# 3020_-0113.net
KiCad netlist of a schematic drawn in EasyEDA Pro
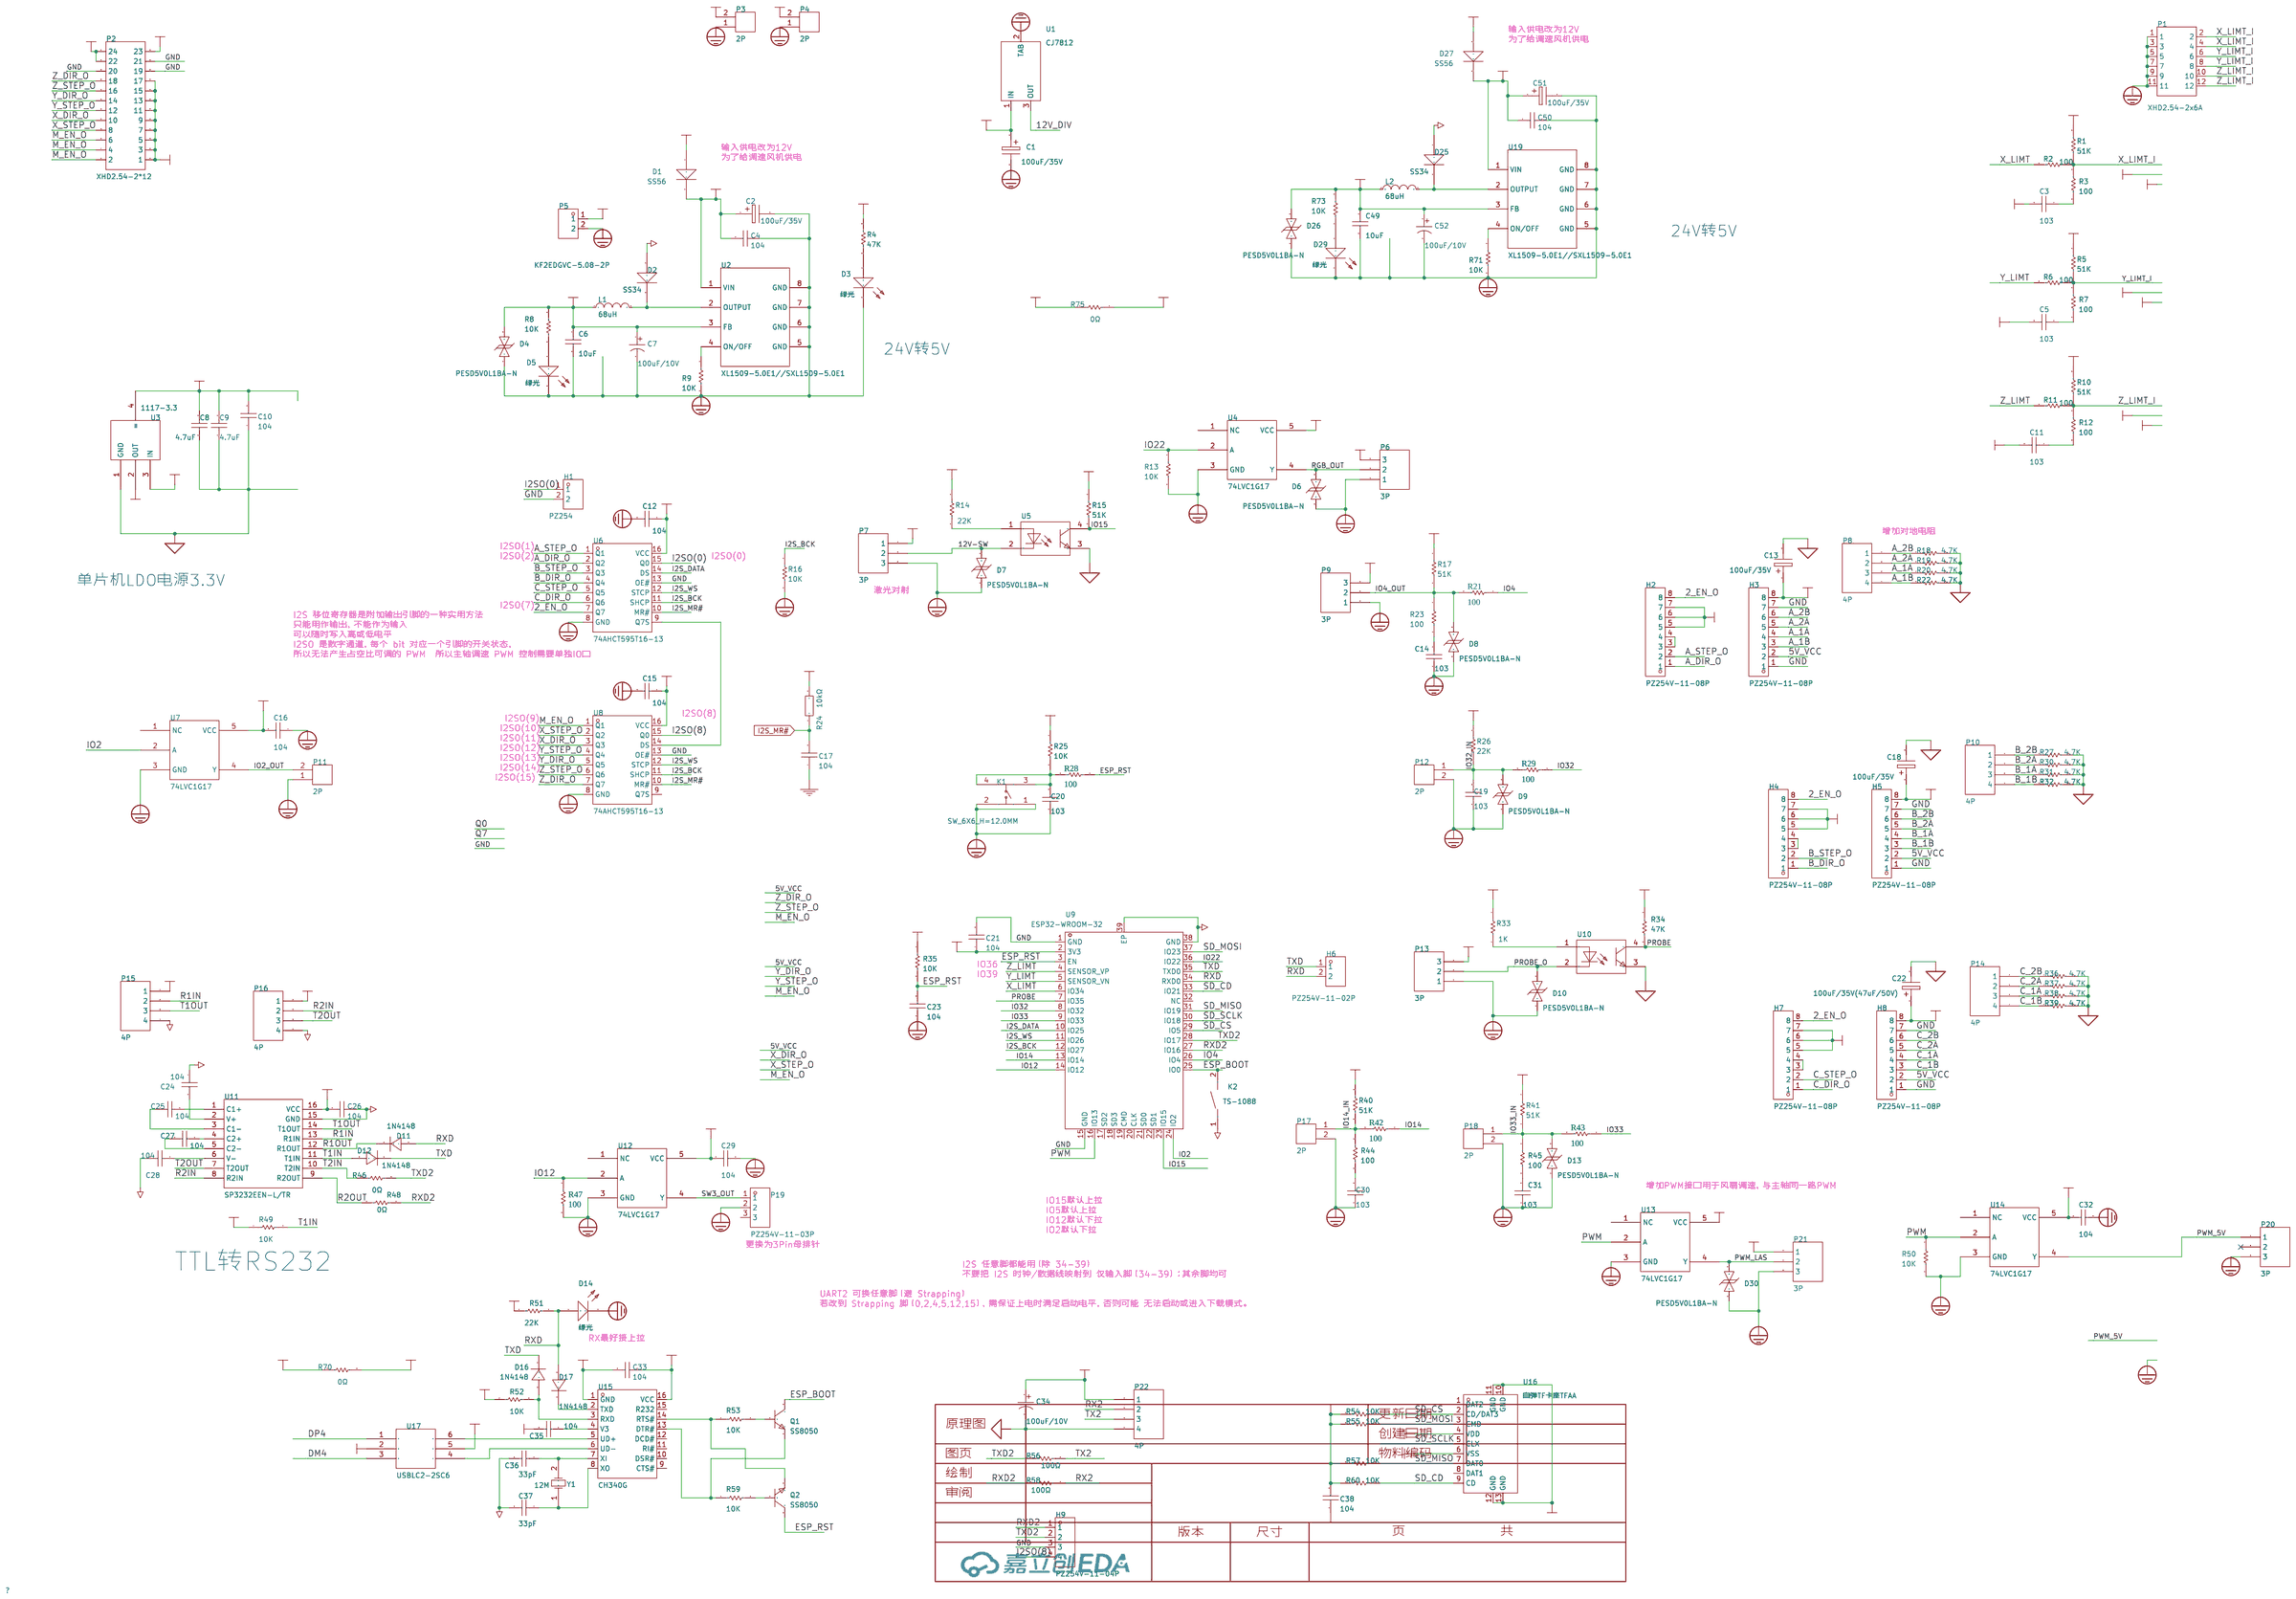
[diagram p0: 电源]
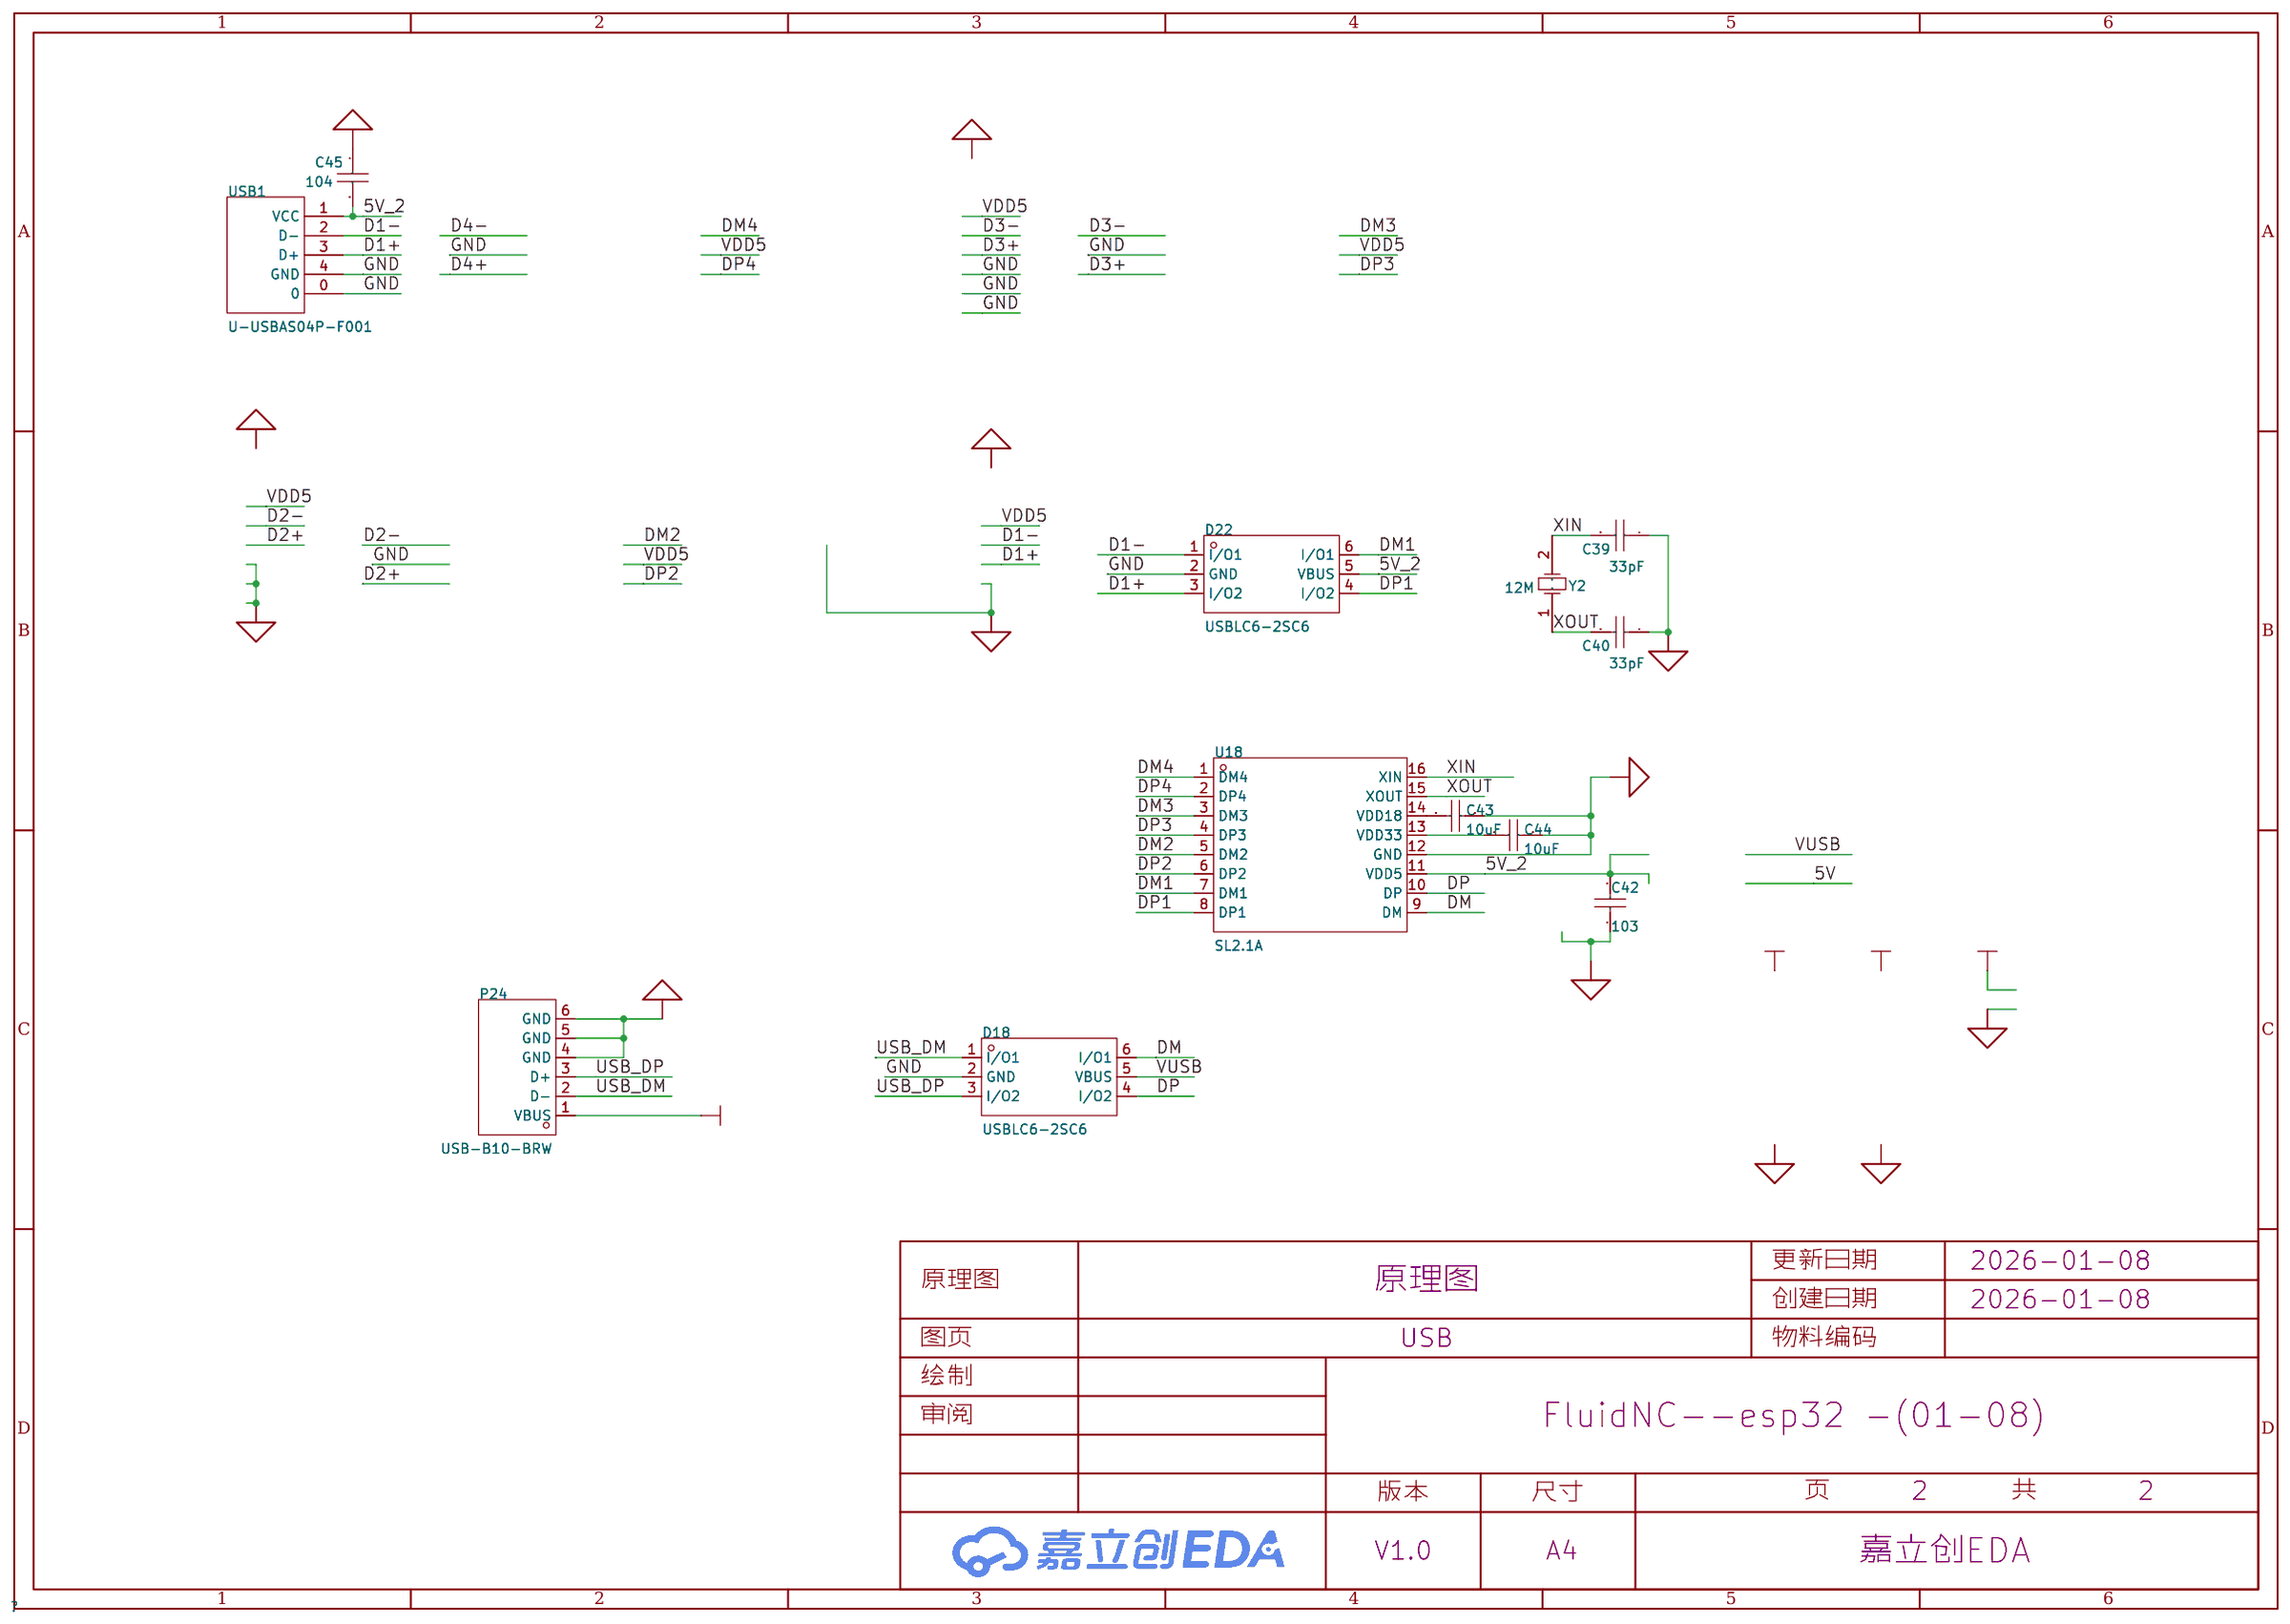
[diagram p1: USB]

(export (version "E")
  (design (tool "Eeschema 10.0.6"))
  (components
    (comp (ref "C1")
      (value "100uF/35V")
      (footprint "easyedapro:电解电容贴片10x10")
      (libsource (lib "easyedapro") (part "ELECTRO1"))
    )
    (comp (ref "C2")
      (value "100uF/35V")
      (footprint "easyedapro:电解电容贴片10x10")
      (libsource (lib "easyedapro") (part "ELECTRO1"))
    )
    (comp (ref "C3") (value "103") (footprint "easyedapro:11") (libsource (lib "") (part "CAP_1")))
    (comp (ref "C4")
      (value "104")
      (footprint "easyedapro:0603C")
      (description "Capacitor (Semiconductor SIM Model)")
      (libsource (lib "easyedapro") (part "Cap Semi"))
    )
    (comp (ref "C5") (value "103") (footprint "easyedapro:11") (libsource (lib "") (part "CAP_1")))
    (comp (ref "C6") (value "10uF") (libsource (lib "easyedapro") (part "CAP")))
    (comp (ref "C7")
      (value "100uF/10V")
      (footprint "easyedapro:CAP-SMD_BD5.0-L5.3-W5.3-RD")
      (fields (field (name "Manufacturer Part") "CS1A101M-CRD54") (field (name "Manufacturer") "ST(先科)"))
      (libsource (lib "easyedapro") (part "CS1A101M-CRD54"))
    )
    (comp (ref "C8") (value "4.7uF") (libsource (lib "easyedapro") (part "CAP")))
    (comp (ref "C9") (value "4.7uF") (libsource (lib "easyedapro") (part "CAP")))
    (comp (ref "C10")
      (value "104")
      (footprint "easyedapro:0603C")
      (description "Capacitor (Semiconductor SIM Model)")
      (libsource (lib "easyedapro") (part "Cap Semi"))
    )
    (comp (ref "C11") (value "103") (footprint "easyedapro:11") (libsource (lib "") (part "CAP_1")))
    (comp (ref "C12")
      (value "104")
      (footprint "easyedapro:0603C")
      (description "Capacitor (Semiconductor SIM Model)")
      (libsource (lib "easyedapro") (part "Cap Semi"))
    )
    (comp (ref "C13")
      (value "100uF/35V")
      (footprint "easyedapro:电解电容贴片10x10")
      (libsource (lib "easyedapro") (part "ELECTRO1"))
    )
    (comp (ref "C14") (value "103") (footprint "easyedapro:11") (libsource (lib "") (part "CAP_1")))
    (comp (ref "C15")
      (value "104")
      (footprint "easyedapro:0603C")
      (description "Capacitor (Semiconductor SIM Model)")
      (libsource (lib "easyedapro") (part "Cap Semi"))
    )
    (comp (ref "C16")
      (value "104")
      (footprint "easyedapro:0603C")
      (description "Capacitor (Semiconductor SIM Model)")
      (libsource (lib "easyedapro") (part "Cap Semi"))
    )
    (comp (ref "C17")
      (value "104")
      (footprint "easyedapro:0603C")
      (description "Capacitor (Semiconductor SIM Model)")
      (libsource (lib "easyedapro") (part "Cap Semi"))
    )
    (comp (ref "C18")
      (value "100uF/35V")
      (footprint "easyedapro:电解电容贴片10x10")
      (libsource (lib "easyedapro") (part "ELECTRO1"))
    )
    (comp (ref "C19") (value "103") (footprint "easyedapro:11") (libsource (lib "") (part "CAP_1")))
    (comp (ref "C20") (value "103") (footprint "easyedapro:11") (libsource (lib "") (part "CAP_1")))
    (comp (ref "C21")
      (value "104")
      (footprint "easyedapro:0603C")
      (description "Capacitor (Semiconductor SIM Model)")
      (libsource (lib "easyedapro") (part "Cap Semi"))
    )
    (comp (ref "C22")
      (value "100uF/35V(47uF/50V)")
      (footprint "easyedapro:电解电容贴片10x10")
      (libsource (lib "easyedapro") (part "ELECTRO1"))
    )
    (comp (ref "C23")
      (value "104")
      (footprint "easyedapro:0603C")
      (description "Capacitor (Semiconductor SIM Model)")
      (libsource (lib "easyedapro") (part "Cap Semi"))
    )
    (comp (ref "C24")
      (value "104")
      (footprint "easyedapro:0603C")
      (description "Capacitor (Semiconductor SIM Model)")
      (libsource (lib "easyedapro") (part "Cap Semi"))
    )
    (comp (ref "C25")
      (value "104")
      (footprint "easyedapro:0603C")
      (description "Capacitor (Semiconductor SIM Model)")
      (libsource (lib "easyedapro") (part "Cap Semi"))
    )
    (comp (ref "C26")
      (value "104")
      (footprint "easyedapro:0603C")
      (description "Capacitor (Semiconductor SIM Model)")
      (libsource (lib "easyedapro") (part "Cap Semi"))
    )
    (comp (ref "C27")
      (value "104")
      (footprint "easyedapro:0603C")
      (description "Capacitor (Semiconductor SIM Model)")
      (libsource (lib "easyedapro") (part "Cap Semi"))
    )
    (comp (ref "C28")
      (value "104")
      (footprint "easyedapro:0603C")
      (description "Capacitor (Semiconductor SIM Model)")
      (libsource (lib "easyedapro") (part "Cap Semi"))
    )
    (comp (ref "C29")
      (value "104")
      (footprint "easyedapro:0603C")
      (description "Capacitor (Semiconductor SIM Model)")
      (libsource (lib "easyedapro") (part "Cap Semi"))
    )
    (comp (ref "C30") (value "103") (footprint "easyedapro:11") (libsource (lib "") (part "CAP_1")))
    (comp (ref "C31") (value "103") (footprint "easyedapro:11") (libsource (lib "") (part "CAP_1")))
    (comp (ref "C32")
      (value "104")
      (footprint "easyedapro:0603C")
      (description "Capacitor (Semiconductor SIM Model)")
      (libsource (lib "easyedapro") (part "Cap Semi"))
    )
    (comp (ref "C33")
      (value "104")
      (footprint "easyedapro:0603C")
      (description "Capacitor (Semiconductor SIM Model)")
      (libsource (lib "easyedapro") (part "Cap Semi"))
    )
    (comp (ref "C34")
      (value "100uF/10V")
      (footprint "easyedapro:CAP-SMD_BD5.0-L5.3-W5.3-RD")
      (fields (field (name "Manufacturer Part") "CS1A101M-CRD54") (field (name "Manufacturer") "ST(先科)"))
      (libsource (lib "easyedapro") (part "CS1A101M-CRD54"))
    )
    (comp (ref "C35")
      (value "104")
      (footprint "easyedapro:0603C")
      (description "Capacitor (Semiconductor SIM Model)")
      (libsource (lib "easyedapro") (part "Cap Semi"))
    )
    (comp (ref "C36")
      (value "18pF")
      (footprint "easyedapro:0603C")
      (description "Capacitor (Semiconductor SIM Model)")
      (libsource (lib "easyedapro") (part "Cap Semi"))
    )
    (comp (ref "C37")
      (value "18pF")
      (footprint "easyedapro:0603C")
      (description "Capacitor (Semiconductor SIM Model)")
      (libsource (lib "easyedapro") (part "Cap Semi"))
    )
    (comp (ref "C38")
      (value "104")
      (footprint "easyedapro:11")
      (description "Capacitor (Semiconductor SIM Model)")
      (libsource (lib "easyedapro") (part "Cap Semi"))
    )
    (comp (ref "C49") (value "10uF") (libsource (lib "easyedapro") (part "CAP")))
    (comp (ref "C50")
      (value "104")
      (footprint "easyedapro:0603C")
      (description "Capacitor (Semiconductor SIM Model)")
      (libsource (lib "easyedapro") (part "Cap Semi"))
    )
    (comp (ref "C51")
      (value "100uF/35V")
      (footprint "easyedapro:电解电容贴片10x10")
      (libsource (lib "easyedapro") (part "ELECTRO1"))
    )
    (comp (ref "C52")
      (value "100uF/10V")
      (footprint "easyedapro:CAP-SMD_BD5.0-L5.3-W5.3-RD")
      (fields (field (name "Manufacturer Part") "CS1A101M-CRD54") (field (name "Manufacturer") "ST(先科)"))
      (libsource (lib "easyedapro") (part "CS1A101M-CRD54"))
    )
    (comp (ref "D1") (value "SS56") (footprint "easyedapro:SMA") (libsource (lib "") (part "1N4148_1")))
    (comp (ref "D2") (value "SS34") (libsource (lib "easyedapro") (part "1N4148")))
    (comp (ref "D3")
      (value "绿光")
      (footprint "easyedapro:0603LED")
      (libsource (lib "easyedapro") (part "LED"))
    )
    (comp (ref "D4")
      (value "PESD5V0L1BA-N")
      (footprint "easyedapro:SOD-523_L1.2-W0.8-LS1.6-BI")
      (description "极性:Bidirectional;反向关断电压（典型值）:5V (Max);击穿电压（最小值）:6V;箝位电压:15V;峰值脉冲电流（10/1000us）:5A (8/20us);")
      (fields (field (name "Manufacturer") "BORN伯恩半导体"))
      (libsource (lib "easyedapro") (part "PESD5V0S1BBN"))
    )
    (comp (ref "D5")
      (value "绿光")
      (footprint "easyedapro:0603LED")
      (libsource (lib "easyedapro") (part "LED"))
    )
    (comp (ref "D6")
      (value "PESD5V0L1BA-N")
      (footprint "easyedapro:SOD-523_L1.2-W0.8-LS1.6-BI")
      (description "极性:Bidirectional;反向关断电压（典型值）:5V (Max);击穿电压（最小值）:6V;箝位电压:15V;峰值脉冲电流（10/1000us）:5A (8/20us);")
      (fields (field (name "Manufacturer") "BORN伯恩半导体"))
      (libsource (lib "easyedapro") (part "PESD5V0S1BBN"))
    )
    (comp (ref "D7")
      (value "PESD5V0L1BA-N")
      (footprint "easyedapro:SOD-523_L1.2-W0.8-LS1.6-BI")
      (description "极性:Bidirectional;反向关断电压（典型值）:5V (Max);击穿电压（最小值）:6V;箝位电压:15V;峰值脉冲电流（10/1000us）:5A (8/20us);")
      (fields (field (name "Manufacturer") "BORN伯恩半导体"))
      (libsource (lib "easyedapro") (part "PESD5V0S1BBN"))
    )
    (comp (ref "D8")
      (value "PESD5V0L1BA-N")
      (footprint "easyedapro:SOD-523_L1.2-W0.8-LS1.6-BI")
      (description "极性:Bidirectional;反向关断电压（典型值）:5V (Max);击穿电压（最小值）:6V;箝位电压:15V;峰值脉冲电流（10/1000us）:5A (8/20us);")
      (fields (field (name "Manufacturer") "BORN伯恩半导体"))
      (libsource (lib "easyedapro") (part "PESD5V0S1BBN"))
    )
    (comp (ref "D9")
      (value "PESD5V0L1BA-N")
      (footprint "easyedapro:SOD-523_L1.2-W0.8-LS1.6-BI")
      (description "极性:Bidirectional;反向关断电压（典型值）:5V (Max);击穿电压（最小值）:6V;箝位电压:15V;峰值脉冲电流（10/1000us）:5A (8/20us);")
      (fields (field (name "Manufacturer") "BORN伯恩半导体"))
      (libsource (lib "easyedapro") (part "PESD5V0S1BBN"))
    )
    (comp (ref "D10")
      (value "PESD5V0L1BA-N")
      (footprint "easyedapro:SOD-523_L1.2-W0.8-LS1.6-BI")
      (description "极性:Bidirectional;反向关断电压（典型值）:5V (Max);击穿电压（最小值）:6V;箝位电压:15V;峰值脉冲电流（10/1000us）:5A (8/20us);")
      (fields (field (name "Manufacturer") "BORN伯恩半导体"))
      (libsource (lib "easyedapro") (part "PESD5V0S1BBN"))
    )
    (comp (ref "D11")
      (value "1N4148")
      (footprint "easyedapro:SOD-123_L2.8-W1.8-LS3.7-RD")
      (fields (field (name "Manufacturer") "VISHAY(威世)"))
      (libsource (lib "easyedapro") (part "1N4148W-E3-08"))
    )
    (comp (ref "D12")
      (value "1N4148")
      (footprint "easyedapro:SOD-123_L2.8-W1.8-LS3.7-RD")
      (fields (field (name "Manufacturer") "VISHAY(威世)"))
      (libsource (lib "easyedapro") (part "1N4148W-E3-08"))
    )
    (comp (ref "D13")
      (value "PESD5V0L1BA-N")
      (footprint "easyedapro:SOD-523_L1.2-W0.8-LS1.6-BI")
      (description "极性:Bidirectional;反向关断电压（典型值）:5V (Max);击穿电压（最小值）:6V;箝位电压:15V;峰值脉冲电流（10/1000us）:5A (8/20us);")
      (fields (field (name "Manufacturer") "BORN伯恩半导体"))
      (libsource (lib "easyedapro") (part "PESD5V0S1BBN"))
    )
    (comp (ref "D14")
      (value "绿光")
      (footprint "easyedapro:0603LED")
      (libsource (lib "easyedapro") (part "LED"))
    )
    (comp (ref "D16")
      (value "1N4148")
      (footprint "easyedapro:SOD-123_L2.8-W1.8-LS3.7-RD")
      (fields (field (name "Manufacturer") "VISHAY(威世)"))
      (libsource (lib "easyedapro") (part "1N4148W-E3-08"))
    )
    (comp (ref "D17")
      (value "1N4148")
      (footprint "easyedapro:SOD-123_L2.8-W1.8-LS3.7-RD")
      (fields (field (name "Manufacturer") "VISHAY(威世)"))
      (libsource (lib "easyedapro") (part "1N4148W-E3-08"))
    )
    (comp (ref "D25") (value "SS34") (libsource (lib "easyedapro") (part "1N4148")))
    (comp (ref "D26")
      (value "PESD5V0L1BA-N")
      (footprint "easyedapro:SOD-523_L1.2-W0.8-LS1.6-BI")
      (description "极性:Bidirectional;反向关断电压（典型值）:5V (Max);击穿电压（最小值）:6V;箝位电压:15V;峰值脉冲电流（10/1000us）:5A (8/20us);")
      (fields (field (name "Manufacturer") "BORN伯恩半导体"))
      (libsource (lib "easyedapro") (part "PESD5V0S1BBN"))
    )
    (comp (ref "D27") (value "SS56") (footprint "easyedapro:SMA") (libsource (lib "") (part "1N4148_1")))
    (comp (ref "D29")
      (value "绿光")
      (footprint "easyedapro:0603LED")
      (libsource (lib "easyedapro") (part "LED"))
    )
    (comp (ref "D30")
      (value "PESD5V0L1BA-N")
      (footprint "easyedapro:SOD-523_L1.2-W0.8-LS1.6-BI")
      (description "极性:Bidirectional;反向关断电压（典型值）:5V (Max);击穿电压（最小值）:6V;箝位电压:15V;峰值脉冲电流（10/1000us）:5A (8/20us);")
      (fields (field (name "Manufacturer") "BORN伯恩半导体"))
      (libsource (lib "easyedapro") (part "PESD5V0S1BBN"))
    )
    (comp (ref "H1")
      (value "PZ254")
      (footprint "easyedapro:HDR-TH_2P-P2.54-V-M")
      (fields (field (name "Manufacturer") "XFCN(兴飞)"))
      (libsource (lib "easyedapro") (part "PZ254V-11-02P"))
    )
    (comp (ref "H2")
      (value "PZ254V-11-08P")
      (footprint "easyedapro:HDR-TH_8P-P2.54-V-M")
      (fields (field (name "Manufacturer") "XFCN(兴飞)"))
      (libsource (lib "easyedapro") (part "PZ254V-11-08P"))
    )
    (comp (ref "H3")
      (value "PZ254V-11-08P")
      (footprint "easyedapro:HDR-TH_8P-P2.54-V-M")
      (fields (field (name "Manufacturer") "XFCN(兴飞)"))
      (libsource (lib "easyedapro") (part "PZ254V-11-08P"))
    )
    (comp (ref "H4")
      (value "PZ254V-11-08P")
      (footprint "easyedapro:HDR-TH_8P-P2.54-V-M")
      (fields (field (name "Manufacturer") "XFCN(兴飞)"))
      (libsource (lib "easyedapro") (part "PZ254V-11-08P"))
    )
    (comp (ref "H5")
      (value "PZ254V-11-08P")
      (footprint "easyedapro:HDR-TH_8P-P2.54-V-M")
      (fields (field (name "Manufacturer") "XFCN(兴飞)"))
      (libsource (lib "easyedapro") (part "PZ254V-11-08P"))
    )
    (comp (ref "H6")
      (value "PZ254V-11-02P")
      (footprint "easyedapro:HDR-TH_2P-P2.54-V-M")
      (fields (field (name "Manufacturer") "XFCN(兴飞)"))
      (libsource (lib "easyedapro") (part "PZ254V-11-02P"))
    )
    (comp (ref "H7")
      (value "PZ254V-11-08P")
      (footprint "easyedapro:HDR-TH_8P-P2.54-V-M")
      (fields (field (name "Manufacturer") "XFCN(兴飞)"))
      (libsource (lib "easyedapro") (part "PZ254V-11-08P"))
    )
    (comp (ref "H8")
      (value "PZ254V-11-08P")
      (footprint "easyedapro:HDR-TH_8P-P2.54-V-M")
      (fields (field (name "Manufacturer") "XFCN(兴飞)"))
      (libsource (lib "easyedapro") (part "PZ254V-11-08P"))
    )
    (comp (ref "H9")
      (value "PZ254V-11-04P")
      (footprint "easyedapro:HDR-TH_4P-P2.54-V-M")
      (fields (field (name "Manufacturer") "XFCN(兴飞)"))
      (libsource (lib "easyedapro") (part "PZ254V-11-04P_C2691448"))
    )
    (comp (ref "K1")
      (value "SW_6X6_H=12.0MM")
      (footprint "easyedapro:KEY-SMD_4P-L6.0-W6.0-P4.50-LS9.0")
      (libsource (lib "easyedapro") (part "SW_6X6_H=12.0MM"))
    )
    (comp (ref "K2")
      (value "TS-1088")
      (footprint "easyedapro:SW-SMD_L3.9-W3.0-P4.45")
      (fields (field (name "Manufacturer") "XUNPU(讯普)"))
      (libsource (lib "easyedapro") (part "TS-1088-AR02016"))
    )
    (comp (ref "L1")
      (value "68uH")
      (footprint "easyedapro:IND-SMD_L7.0-W7.0_SMDRI74-330MT")
      (description "电感值:33uH;精度:±20%;额定电流:960mA;饱和电流(Isat):1.8A;类型:屏蔽电感;")
      (fields (field (name "Manufacturer Part") "SMDRI74-330MT") (field (name "Manufacturer") "SXN(顺翔诺)"))
      (libsource (lib "easyedapro") (part "SMDRI74-330MT"))
    )
    (comp (ref "L2")
      (value "68uH")
      (footprint "easyedapro:IND-SMD_L7.0-W7.0_SMDRI74-330MT")
      (description "电感值:33uH;精度:±20%;额定电流:960mA;饱和电流(Isat):1.8A;类型:屏蔽电感;")
      (fields (field (name "Manufacturer Part") "SMDRI74-330MT") (field (name "Manufacturer") "SXN(顺翔诺)"))
      (libsource (lib "easyedapro") (part "SMDRI74-330MT"))
    )
    (comp (ref "P1")
      (value "XHD2.54-2x6A")
      (footprint "easyedapro:CONN-TH_12P-P2.50_HC-XHD2.54-2X6A")
      (fields (field (name "Manufacturer") "HC(虹成电子)"))
      (libsource (lib "easyedapro") (part "HC-XHD2.54-2X6A"))
    )
    (comp (ref "P2")
      (value "XHD2.54-2*12")
      (footprint "easyedapro:IDC-TH_24P-P2.54-V-R2-C12-S2.54")
      (fields (field (name "Manufacturer") "BOOMELE(博穆精密)"))
      (libsource (lib "easyedapro") (part "HDR-IDC-2.54-2X12P"))
    )
    (comp (ref "P3") (value "2P") (libsource (lib "easyedapro") (part "2P")))
    (comp (ref "P4") (value "2P") (libsource (lib "easyedapro") (part "2P")))
    (comp (ref "P5")
      (value "KF2EDGVC-5.08-2P")
      (footprint "easyedapro:CONN-TH_P5.08_KF2EDGVC-5.08-2P")
      (description "连接器类型:板端/插座-闭口;结构:1x2P;间距:5.08mm;颜色:绿色;安装方式:直针;排数:1;每排PIN数:2;额定电流:15A;额定电压:300V;工作温度:-40°C~+105°C;")
      (fields (field (name "Manufacturer") "KEFA(科发)"))
      (libsource (lib "easyedapro") (part "KF2EDGVC-5.08-2P"))
    )
    (comp (ref "P6")
      (value "3P")
      (footprint "easyedapro:HDR1X3_CON")
      (libsource (lib "easyedapro") (part "3P"))
    )
    (comp (ref "P7")
      (value "3P")
      (footprint "easyedapro:HDR1X3_CON")
      (libsource (lib "easyedapro") (part "3P"))
    )
    (comp (ref "P8")
      (value "4P")
      (footprint "easyedapro:HDR1X4_CON")
      (libsource (lib "easyedapro") (part "4P"))
    )
    (comp (ref "P9")
      (value "3P")
      (footprint "easyedapro:HDR1X3_CON")
      (libsource (lib "easyedapro") (part "3P"))
    )
    (comp (ref "P10")
      (value "4P")
      (footprint "easyedapro:HDR1X4_CON")
      (libsource (lib "easyedapro") (part "4P"))
    )
    (comp (ref "P11") (value "2P") (libsource (lib "easyedapro") (part "2P")))
    (comp (ref "P12") (value "2P") (libsource (lib "easyedapro") (part "2P")))
    (comp (ref "P13")
      (value "3P")
      (footprint "easyedapro:HDR1X3_CON")
      (libsource (lib "easyedapro") (part "3P"))
    )
    (comp (ref "P14")
      (value "4P")
      (footprint "easyedapro:HDR1X4_CON")
      (libsource (lib "easyedapro") (part "4P"))
    )
    (comp (ref "P15")
      (value "4P")
      (footprint "easyedapro:HDR1X4_CON")
      (libsource (lib "easyedapro") (part "4P"))
    )
    (comp (ref "P16")
      (value "4P")
      (footprint "easyedapro:HDR1X4_CON")
      (libsource (lib "easyedapro") (part "4P"))
    )
    (comp (ref "P17") (value "2P") (libsource (lib "easyedapro") (part "2P")))
    (comp (ref "P18") (value "2P") (libsource (lib "easyedapro") (part "2P")))
    (comp (ref "P19")
      (value "PZ254V-11-03P")
      (footprint "easyedapro:HDR-TH_3P-P2.54-V-M")
      (fields (field (name "Manufacturer") "XFCN(兴飞)"))
      (libsource (lib "easyedapro") (part "PZ254V-11-03P"))
    )
    (comp (ref "P20")
      (value "3P")
      (footprint "easyedapro:HDR1X3_CON")
      (libsource (lib "easyedapro") (part "3P"))
    )
    (comp (ref "P21")
      (value "3P")
      (footprint "easyedapro:HDR1X3_CON")
      (libsource (lib "easyedapro") (part "3P"))
    )
    (comp (ref "P22")
      (value "4P")
      (footprint "easyedapro:HDR1X4_CON")
      (libsource (lib "easyedapro") (part "4P"))
    )
    (comp (ref "Q1")
      (value "SS8050")
      (footprint "easyedapro:SOT-23-3_L2.9-W1.3-P1.90-LS2.4-BR")
      (fields (field (name "Manufacturer") "Doeshare(德芯)"))
      (libsource (lib "easyedapro") (part "SS8050_C2931717"))
    )
    (comp (ref "Q2")
      (value "SS8050")
      (footprint "easyedapro:SOT-23-3_L2.9-W1.3-P1.90-LS2.4-BR")
      (fields (field (name "Manufacturer") "Doeshare(德芯)"))
      (libsource (lib "easyedapro") (part "SS8050_C2931717"))
    )
    (comp (ref "R1")
      (value "51K")
      (footprint "easyedapro:10")
      (description "Resistor")
      (libsource (lib "easyedapro") (part "RES"))
    )
    (comp (ref "R2")
      (value "100")
      (footprint "easyedapro:10")
      (description "Resistor")
      (libsource (lib "easyedapro") (part "RES"))
    )
    (comp (ref "R3")
      (value "100")
      (footprint "easyedapro:10")
      (description "Resistor")
      (libsource (lib "easyedapro") (part "RES"))
    )
    (comp (ref "R4")
      (value "47K")
      (footprint "easyedapro:0603R")
      (description "Resistor")
      (libsource (lib "easyedapro") (part "RES"))
    )
    (comp (ref "R5")
      (value "51K")
      (footprint "easyedapro:10")
      (description "Resistor")
      (libsource (lib "easyedapro") (part "RES"))
    )
    (comp (ref "R6")
      (value "100")
      (footprint "easyedapro:10")
      (description "Resistor")
      (libsource (lib "easyedapro") (part "RES"))
    )
    (comp (ref "R7")
      (value "100")
      (footprint "easyedapro:10")
      (description "Resistor")
      (libsource (lib "easyedapro") (part "RES"))
    )
    (comp (ref "R8")
      (value "10K")
      (footprint "easyedapro:0603R")
      (description "Resistor")
      (libsource (lib "easyedapro") (part "RES"))
    )
    (comp (ref "R9")
      (value "10K")
      (footprint "easyedapro:0603R")
      (description "Resistor")
      (libsource (lib "easyedapro") (part "RES"))
    )
    (comp (ref "R10")
      (value "51K")
      (footprint "easyedapro:10")
      (description "Resistor")
      (libsource (lib "easyedapro") (part "RES"))
    )
    (comp (ref "R11")
      (value "100")
      (footprint "easyedapro:10")
      (description "Resistor")
      (libsource (lib "easyedapro") (part "RES"))
    )
    (comp (ref "R12")
      (value "100")
      (footprint "easyedapro:10")
      (description "Resistor")
      (libsource (lib "easyedapro") (part "RES"))
    )
    (comp (ref "R13")
      (value "10K")
      (description "Resistor")
      (fields (field (name "Publisher") "Altium Limited"))
      (libsource (lib "") (part "RES_1"))
    )
    (comp (ref "R14")
      (value "22K")
      (footprint "easyedapro:0603R")
      (description "Resistor")
      (libsource (lib "easyedapro") (part "RES"))
    )
    (comp (ref "R15")
      (value "10K")
      (footprint "easyedapro:0603R")
      (description "Resistor")
      (libsource (lib "easyedapro") (part "RES"))
    )
    (comp (ref "R16")
      (value "10K")
      (footprint "easyedapro:0603R")
      (description "Resistor")
      (libsource (lib "easyedapro") (part "RES"))
    )
    (comp (ref "R17")
      (value "10K")
      (footprint "easyedapro:0603R")
      (description "Resistor")
      (libsource (lib "easyedapro") (part "RES"))
    )
    (comp (ref "R18")
      (value "10K")
      (footprint "easyedapro:0603R")
      (description "Resistor")
      (libsource (lib "easyedapro") (part "10K"))
    )
    (comp (ref "R19")
      (value "10K")
      (footprint "easyedapro:0603R")
      (description "Resistor")
      (libsource (lib "easyedapro") (part "10K"))
    )
    (comp (ref "R20")
      (value "10K")
      (footprint "easyedapro:0603R")
      (description "Resistor")
      (libsource (lib "easyedapro") (part "10K"))
    )
    (comp (ref "R21")
      (value "100")
      (description "Resistor")
      (fields (field (name "Publisher") "Altium Limited"))
      (libsource (lib "") (part "RES_1"))
    )
    (comp (ref "R22")
      (value "10K")
      (footprint "easyedapro:0603R")
      (description "Resistor")
      (libsource (lib "easyedapro") (part "10K"))
    )
    (comp (ref "R23")
      (value "100")
      (footprint "easyedapro:10")
      (description "Resistor")
      (libsource (lib "easyedapro") (part "RES"))
    )
    (comp (ref "R24")
      (value "10kΩ")
      (footprint "easyedapro:R0603")
      (fields (field (name "Manufacturer Part") "0603WAF1002T5E") (field (name "Manufacturer") "UniOhm"))
      (libsource (lib "easyedapro") (part "10kΩ"))
    )
    (comp (ref "R25")
      (value "10K")
      (footprint "easyedapro:0603R")
      (description "Resistor")
      (libsource (lib "easyedapro") (part "RES"))
    )
    (comp (ref "R26")
      (value "10K")
      (footprint "easyedapro:0603R")
      (description "Resistor")
      (libsource (lib "easyedapro") (part "RES"))
    )
    (comp (ref "R27")
      (value "10K")
      (footprint "easyedapro:0603R")
      (description "Resistor")
      (libsource (lib "easyedapro") (part "10K"))
    )
    (comp (ref "R28")
      (value "100")
      (description "Resistor")
      (fields (field (name "Publisher") "Altium Limited"))
      (libsource (lib "") (part "RES_1"))
    )
    (comp (ref "R29")
      (value "100")
      (description "Resistor")
      (fields (field (name "Publisher") "Altium Limited"))
      (libsource (lib "") (part "RES_1"))
    )
    (comp (ref "R30")
      (value "10K")
      (footprint "easyedapro:0603R")
      (description "Resistor")
      (libsource (lib "easyedapro") (part "10K"))
    )
    (comp (ref "R31")
      (value "10K")
      (footprint "easyedapro:0603R")
      (description "Resistor")
      (libsource (lib "easyedapro") (part "10K"))
    )
    (comp (ref "R32")
      (value "10K")
      (footprint "easyedapro:0603R")
      (description "Resistor")
      (libsource (lib "easyedapro") (part "10K"))
    )
    (comp (ref "R33")
      (value "1K")
      (footprint "easyedapro:0603R")
      (description "Resistor")
      (libsource (lib "easyedapro") (part "RES"))
    )
    (comp (ref "R34")
      (value "10K")
      (footprint "easyedapro:0603R")
      (description "Resistor")
      (libsource (lib "easyedapro") (part "RES"))
    )
    (comp (ref "R35")
      (value "10K")
      (footprint "easyedapro:0603R")
      (description "Resistor")
      (libsource (lib "easyedapro") (part "RES"))
    )
    (comp (ref "R36")
      (value "10K")
      (footprint "easyedapro:0603R")
      (description "Resistor")
      (libsource (lib "easyedapro") (part "10K"))
    )
    (comp (ref "R37")
      (value "10K")
      (footprint "easyedapro:0603R")
      (description "Resistor")
      (libsource (lib "easyedapro") (part "10K"))
    )
    (comp (ref "R38")
      (value "10K")
      (footprint "easyedapro:0603R")
      (description "Resistor")
      (libsource (lib "easyedapro") (part "10K"))
    )
    (comp (ref "R39")
      (value "10K")
      (footprint "easyedapro:0603R")
      (description "Resistor")
      (libsource (lib "easyedapro") (part "10K"))
    )
    (comp (ref "R40")
      (value "10K")
      (footprint "easyedapro:0603R")
      (description "Resistor")
      (libsource (lib "easyedapro") (part "RES"))
    )
    (comp (ref "R41")
      (value "10K")
      (footprint "easyedapro:0603R")
      (description "Resistor")
      (libsource (lib "easyedapro") (part "RES"))
    )
    (comp (ref "R42")
      (value "100")
      (description "Resistor")
      (fields (field (name "Publisher") "Altium Limited"))
      (libsource (lib "") (part "RES_1"))
    )
    (comp (ref "R43")
      (value "100")
      (description "Resistor")
      (fields (field (name "Publisher") "Altium Limited"))
      (libsource (lib "") (part "RES_1"))
    )
    (comp (ref "R44")
      (value "100")
      (footprint "easyedapro:10")
      (description "Resistor")
      (libsource (lib "easyedapro") (part "RES"))
    )
    (comp (ref "R45")
      (value "100")
      (footprint "easyedapro:10")
      (description "Resistor")
      (libsource (lib "easyedapro") (part "RES"))
    )
    (comp (ref "R46")
      (value "0Ω")
      (footprint "easyedapro:0603R")
      (description "Resistor")
      (libsource (lib "easyedapro") (part "RES"))
    )
    (comp (ref "R47")
      (value "100")
      (description "Resistor")
      (fields (field (name "Publisher") "Altium Limited"))
      (libsource (lib "") (part "RES_1"))
    )
    (comp (ref "R48")
      (value "0Ω")
      (footprint "easyedapro:0603R")
      (description "Resistor")
      (libsource (lib "easyedapro") (part "RES"))
    )
    (comp (ref "R49")
      (value "10K")
      (footprint "easyedapro:0603R")
      (description "Resistor")
      (libsource (lib "easyedapro") (part "RES"))
    )
    (comp (ref "R50")
      (value "10K")
      (description "Resistor")
      (fields (field (name "Publisher") "Altium Limited"))
      (libsource (lib "") (part "RES_1"))
    )
    (comp (ref "R51")
      (value "10K")
      (footprint "easyedapro:0603R")
      (description "Resistor")
      (libsource (lib "easyedapro") (part "RES"))
    )
    (comp (ref "R52")
      (value "10K")
      (footprint "easyedapro:0603R")
      (description "Resistor")
      (libsource (lib "easyedapro") (part "RES"))
    )
    (comp (ref "R53")
      (value "10K")
      (footprint "easyedapro:0603R")
      (description "Resistor")
      (libsource (lib "easyedapro") (part "RES"))
    )
    (comp (ref "R54")
      (value "10K")
      (footprint "easyedapro:10")
      (description "Resistor")
      (libsource (lib "easyedapro") (part "RES"))
    )
    (comp (ref "R55")
      (value "10K")
      (footprint "easyedapro:10")
      (description "Resistor")
      (libsource (lib "easyedapro") (part "RES"))
    )
    (comp (ref "R56")
      (value "100Ω")
      (footprint "easyedapro:0603R")
      (description "Resistor")
      (libsource (lib "easyedapro") (part "RES"))
    )
    (comp (ref "R57")
      (value "10K")
      (footprint "easyedapro:10")
      (description "Resistor")
      (libsource (lib "easyedapro") (part "RES"))
    )
    (comp (ref "R58")
      (value "100Ω")
      (footprint "easyedapro:0603R")
      (description "Resistor")
      (libsource (lib "easyedapro") (part "RES"))
    )
    (comp (ref "R59")
      (value "10K")
      (footprint "easyedapro:0603R")
      (description "Resistor")
      (libsource (lib "easyedapro") (part "RES"))
    )
    (comp (ref "R60")
      (value "10K")
      (footprint "easyedapro:10")
      (description "Resistor")
      (libsource (lib "easyedapro") (part "RES"))
    )
    (comp (ref "R70")
      (value "0Ω")
      (footprint "easyedapro:0603R")
      (description "Resistor")
      (libsource (lib "easyedapro") (part "RES"))
    )
    (comp (ref "R71")
      (value "10K")
      (footprint "easyedapro:0603R")
      (description "Resistor")
      (libsource (lib "easyedapro") (part "RES"))
    )
    (comp (ref "R73")
      (value "10K")
      (footprint "easyedapro:0603R")
      (description "Resistor")
      (libsource (lib "easyedapro") (part "RES"))
    )
    (comp (ref "R75")
      (value "0Ω")
      (footprint "easyedapro:0603R")
      (description "Resistor")
      (libsource (lib "easyedapro") (part "RES"))
    )
    (comp (ref "U1")
      (value "CJ7812")
      (footprint "easyedapro:TO-263-2_L10.1-W9.1-P5.08-LS15.2-TL")
      (description "输出类型:固定;工作电压:35V;输出电压:12V;输出电流:1.5A;电源纹波抑制比(PSRR):71dB@(120Hz);输出极性:正极;")
      (fields (field (name "Manufacturer") "CJ(江苏长电/长晶)"))
      (libsource (lib "easyedapro") (part "CJ7812_C145151"))
    )
    (comp (ref "U2")
      (value "XL1509-5.0E1//SXL1509-5.0E1")
      (footprint "easyedapro:SOIC-8_L5.0-W4.0-P1.27-LS6.0-BL")
      (description "功能类型:降压型;同步整流:-;输出通道数:-;拓扑结构:-;输入电压:-;输出电流(最大值):-;开关频率:-;")
      (fields (field (name "Manufacturer") "XLSEMI(芯龙)"))
      (libsource (lib "easyedapro") (part "XL1509-5.0E1"))
    )
    (comp (ref "U3")
      (value "1117-3.3")
      (footprint "easyedapro:SOT-223")
      (libsource (lib "easyedapro") (part "LM1117"))
    )
    (comp (ref "U4")
      (value "74LVC1G17")
      (footprint "easyedapro:SMD8")
      (libsource (lib "easyedapro") (part "74LVC1G04"))
    )
    (comp (ref "U5")
      (value "LTV-357T-C")
      (footprint "easyedapro:SOP-4_L4.4-W3.9-P2.54-LS7.0-TL")
      (fields (field (name "Manufacturer") "LITEON(光宝)"))
      (libsource (lib "easyedapro") (part "LTV-357T-C"))
    )
    (comp (ref "U6")
      (value "74AHCT595T16-13")
      (footprint "easyedapro:TSSOP-16_L5.0-W4.4-P0.65-LS6.4-BL")
      (description "功能:串行至串行或并行;工作电压:4.5V~5.5V;元件数:1;每个元件位数:8;")
      (fields (field (name "Manufacturer") "DIODES(美台)"))
      (libsource (lib "easyedapro") (part "74AHCT595T16-13"))
    )
    (comp (ref "U7")
      (value "74LVC1G17")
      (footprint "easyedapro:SMD8")
      (libsource (lib "easyedapro") (part "74LVC1G04"))
    )
    (comp (ref "U8")
      (value "74AHCT595T16-13")
      (footprint "easyedapro:TSSOP-16_L5.0-W4.4-P0.65-LS6.4-BL")
      (description "功能:串行至串行或并行;工作电压:4.5V~5.5V;元件数:1;每个元件位数:8;")
      (fields (field (name "Manufacturer") "DIODES(美台)"))
      (libsource (lib "easyedapro") (part "74AHCT595T16-13"))
    )
    (comp (ref "U9")
      (value "ESP32-WROOM-32")
      (footprint "easyedapro:WIFIM-SMD_ESP-WROOM-32")
      (description "WiFi+双模蓝牙 双核CPU 网口 顶配MCU 低功耗蓝牙 ESP32系列ESP-WROOM-32模组/ESP-32S 4MB")
      (fields (field (name "Manufacturer") "ESPRESSIF(乐鑫)"))
      (libsource (lib "easyedapro") (part "ESP-WROOM-32"))
    )
    (comp (ref "U10")
      (value "LTV-357T-C")
      (footprint "easyedapro:SOP-4_L4.4-W3.9-P2.54-LS7.0-TL")
      (fields (field (name "Manufacturer") "LITEON(光宝)"))
      (libsource (lib "easyedapro") (part "LTV-357T-C"))
    )
    (comp (ref "U11")
      (value "SP3232EEN-L/TR")
      (footprint "easyedapro:SOIC-16_L9.9-W3.9-P1.27-LS6.0-BL")
      (description "类型:收发器;数据速率:235Kbps;")
      (fields (field (name "Manufacturer") "MaxLinear(迈凌)"))
      (libsource (lib "easyedapro") (part "SP3232EEN-L/TR"))
    )
    (comp (ref "U12")
      (value "74LVC1G17")
      (footprint "easyedapro:SMD8")
      (libsource (lib "easyedapro") (part "74LVC1G04"))
    )
    (comp (ref "U13")
      (value "74LVC1G17")
      (footprint "easyedapro:SMD8")
      (libsource (lib "easyedapro") (part "74LVC1G04"))
    )
    (comp (ref "U14")
      (value "74LVC1G17")
      (footprint "easyedapro:SMD8")
      (libsource (lib "easyedapro") (part "74LVC1G04"))
    )
    (comp (ref "U15")
      (value "CH340G")
      (footprint "easyedapro:SOIC-16_L9.9-W3.9-P1.27-LS6.0-BL")
      (description "应用功能:收发器;接口协议:USB 2.0;数据速率:2Mbps;")
      (fields (field (name "Manufacturer") "WCH(南京沁恒)"))
      (libsource (lib "easyedapro") (part "CH340G"))
    )
    (comp (ref "U16")
      (value "自弹TF卡座TFAA")
      (footprint "easyedapro:SIM-SMD_C9900015645")
      (libsource (lib "easyedapro") (part "自弹TF卡座TFAA"))
    )
    (comp (ref "U17")
      (value "USBLC2-2SC6")
      (footprint "easyedapro:SOT-23-6")
      (libsource (lib "easyedapro") (part "DIP6"))
    )
    (comp (ref "U19")
      (value "XL1509-5.0E1//SXL1509-5.0E1")
      (footprint "easyedapro:SOIC-8_L5.0-W4.0-P1.27-LS6.0-BL")
      (description "功能类型:降压型;同步整流:-;输出通道数:-;拓扑结构:-;输入电压:-;输出电流(最大值):-;开关频率:-;")
      (fields (field (name "Manufacturer") "XLSEMI(芯龙)"))
      (libsource (lib "easyedapro") (part "XL1509-5.0E1"))
    )
    (comp (ref "Y1")
      (value "12M")
      (footprint "easyedapro:晶振贴片49SSMD")
      (description "Crystal Oscillator")
      (libsource (lib "easyedapro") (part "XTAL"))
    )
    (comp (ref "C39")
      (value "18pF")
      (footprint "easyedapro:0603C")
      (description "Capacitor (Semiconductor SIM Model)")
      (libsource (lib "easyedapro") (part "Cap Semi"))
    )
    (comp (ref "C40")
      (value "18pF")
      (footprint "easyedapro:0603C")
      (description "Capacitor (Semiconductor SIM Model)")
      (libsource (lib "easyedapro") (part "Cap Semi"))
    )
    (comp (ref "C42") (value "103") (footprint "easyedapro:11") (libsource (lib "") (part "CAP_1")))
    (comp (ref "C43") (value "10uF") (libsource (lib "easyedapro") (part "CAP")))
    (comp (ref "C44") (value "10uF") (libsource (lib "easyedapro") (part "CAP")))
    (comp (ref "C45")
      (value "18pF")
      (footprint "easyedapro:0603C")
      (description "Capacitor (Semiconductor SIM Model)")
      (libsource (lib "easyedapro") (part "Cap Semi"))
    )
    (comp (ref "D18")
      (value "USBLC6-2SC6")
      (footprint "easyedapro:SOT-23-6_L2.9-W1.6-P0.95-LS2.8-BL")
      (description "最大钳位电压:15V;击穿电压:6V;")
      (fields (field (name "Manufacturer") "UMW(友台半导体)"))
      (libsource (lib "easyedapro") (part "USBLC6-2SC6_C2687116"))
    )
    (comp (ref "D22")
      (value "USBLC6-2SC6")
      (footprint "easyedapro:SOT-23-6_L2.9-W1.6-P0.95-LS2.8-BL")
      (description "最大钳位电压:15V;击穿电压:6V;")
      (fields (field (name "Manufacturer") "UMW(友台半导体)"))
      (libsource (lib "easyedapro") (part "USBLC6-2SC6_C2687116"))
    )
    (comp (ref "P24")
      (value "USB-B10-BRW")
      (footprint "easyedapro:USB-B-TH_USB-B10-BRW")
      (fields (field (name "Manufacturer") "XUNPU(讯普)"))
      (libsource (lib "easyedapro") (part "USB-B10-BRW"))
    )
    (comp (ref "U18")
      (value "SL2.1A")
      (footprint "easyedapro:SOP-16_L10.0-W3.9-P1.27-LS6.0-BL")
      (description "SL2.1A是一颗高集成度,高性能,低功耗的USB2.0集线器主控芯片，支持USB2.0高速(480MHz),全速(12MHz)和低速模式(1.5MHz)，内置12MHz晶体振荡器。")
      (fields (field (name "Manufacturer") "CoreChips(和芯润德)"))
      (libsource (lib "easyedapro") (part "SL2.1A"))
    )
    (comp (ref "USB1")
      (value "U-USBAS04P-F001")
      (footprint "easyedapro:USB-A-TH_USB-M-22")
      (description "连接器类型:Type-A;协议标准:USB 2.0;公母:母;安装方式:直插;触点数量:4P;端口数量:1;额定电流 - 电源:1.5A;工作温度:0°C~+50°C;")
      (fields (field (name "Manufacturer") "Ckmtw(灿科盟)"))
      (libsource (lib "easyedapro") (part "U-USBAS04P-F001"))
    )
    (comp (ref "Y2")
      (value "12M")
      (footprint "easyedapro:晶振贴片49SSMD")
      (description "Crystal Oscillator")
      (libsource (lib "easyedapro") (part "XTAL"))
    )
  )
  (nets
    (net (code "1") (name "2_EN_O") (class "Default")
      (node (ref "H2") (pin "8") (pinfunction "8_8") (pintype "unspecified"))
      (node (ref "H4") (pin "8") (pinfunction "8_8") (pintype "unspecified"))
      (node (ref "H7") (pin "8") (pinfunction "8_8") (pintype "unspecified"))
      (node (ref "U6") (pin "7") (pinfunction "Q7_7") (pintype "unspecified"))
    )
    (net (code "2") (name "3V3") (class "Default")
      (node (ref "C10") (pin "2") (pinfunction "2_2") (pintype "unspecified"))
      (node (ref "C21") (pin "1") (pinfunction "1_1") (pintype "unspecified"))
      (node (ref "C38") (pin "2") (pinfunction "2_2") (pintype "unspecified"))
      (node (ref "C8") (pin "2") (pinfunction "2_2") (pintype "input"))
      (node (ref "C9") (pin "2") (pinfunction "2_2") (pintype "input"))
      (node (ref "R25") (pin "1") (pinfunction "1_1") (pintype "unspecified"))
      (node (ref "R35") (pin "1") (pinfunction "1_1") (pintype "unspecified"))
      (node (ref "R51") (pin "2") (pinfunction "2_2") (pintype "unspecified"))
      (node (ref "R54") (pin "2") (pinfunction "2_2") (pintype "unspecified"))
      (node (ref "R55") (pin "2") (pinfunction "2_2") (pintype "unspecified"))
      (node (ref "R57") (pin "2") (pinfunction "2_2") (pintype "unspecified"))
      (node (ref "R60") (pin "2") (pinfunction "2_2") (pintype "unspecified"))
      (node (ref "U16") (pin "4") (pinfunction "VDD_4") (pintype "unspecified"))
      (node (ref "U3") (pin "2") (pinfunction "OUT_2") (pintype "unspecified"))
      (node (ref "U3") (pin "4") (pinfunction "=_4") (pintype "unspecified"))
      (node (ref "U9") (pin "2") (pinfunction "3V3_2") (pintype "unspecified"))
    )
    (net (code "4") (name "5V_2") (class "Default")
      (node (ref "C42") (pin "2") (pinfunction "2_2") (pintype "unspecified"))
      (node (ref "C45") (pin "2") (pinfunction "2_2") (pintype "unspecified"))
      (node (ref "C49") (pin "1") (pinfunction "1_1") (pintype "input"))
      (node (ref "C52") (pin "1") (pinfunction "1_1") (pintype "input"))
      (node (ref "D22") (pin "5") (pinfunction "VBUS_5") (pintype "unspecified"))
      (node (ref "D26") (pin "2") (pinfunction "2_2") (pintype "input"))
      (node (ref "L2") (pin "1") (pinfunction "1_1") (pintype "unspecified"))
      (node (ref "R73") (pin "2") (pinfunction "2_2") (pintype "unspecified"))
      (node (ref "R75") (pin "1") (pinfunction "1_1") (pintype "unspecified"))
      (node (ref "U18") (pin "11") (pinfunction "VDD5_11") (pintype "unspecified"))
      (node (ref "U19") (pin "3") (pinfunction "FB_3") (pintype "input"))
      (node (ref "USB1") (pin "1") (pinfunction "VCC_1") (pintype "unspecified"))
    )
    (net (code "5") (name "5V_VCC") (class "Default")
      (node (ref "C12") (pin "1") (pinfunction "1_1") (pintype "unspecified"))
      (node (ref "C15") (pin "1") (pinfunction "1_1") (pintype "unspecified"))
      (node (ref "C16") (pin "2") (pinfunction "2_2") (pintype "unspecified"))
      (node (ref "C26") (pin "2") (pinfunction "2_2") (pintype "unspecified"))
      (node (ref "C29") (pin "2") (pinfunction "2_2") (pintype "unspecified"))
      (node (ref "C32") (pin "2") (pinfunction "2_2") (pintype "unspecified"))
      (node (ref "C33") (pin "1") (pinfunction "1_1") (pintype "unspecified"))
      (node (ref "C34") (pin "1") (pinfunction "1_1") (pintype "input"))
      (node (ref "C6") (pin "1") (pinfunction "1_1") (pintype "input"))
      (node (ref "C7") (pin "1") (pinfunction "1_1") (pintype "input"))
      (node (ref "D4") (pin "2") (pinfunction "2_2") (pintype "input"))
      (node (ref "H2") (pin "5") (pinfunction "5_5") (pintype "unspecified"))
      (node (ref "H2") (pin "6") (pinfunction "6_6") (pintype "unspecified"))
      (node (ref "H2") (pin "7") (pinfunction "7_7") (pintype "unspecified"))
      (node (ref "H3") (pin "2") (pinfunction "2_2") (pintype "unspecified"))
      (node (ref "H4") (pin "5") (pinfunction "5_5") (pintype "unspecified"))
      (node (ref "H4") (pin "6") (pinfunction "6_6") (pintype "unspecified"))
      (node (ref "H4") (pin "7") (pinfunction "7_7") (pintype "unspecified"))
      (node (ref "H5") (pin "2") (pinfunction "2_2") (pintype "unspecified"))
      (node (ref "H7") (pin "5") (pinfunction "5_5") (pintype "unspecified"))
      (node (ref "H7") (pin "6") (pinfunction "6_6") (pintype "unspecified"))
      (node (ref "H7") (pin "7") (pinfunction "7_7") (pintype "unspecified"))
      (node (ref "H8") (pin "2") (pinfunction "2_2") (pintype "unspecified"))
      (node (ref "L1") (pin "1") (pinfunction "1_1") (pintype "unspecified"))
      (node (ref "P13") (pin "3") (pinfunction "3_3") (pintype "unspecified"))
      (node (ref "P2") (pin "1") (pinfunction "1_1") (pintype "unspecified"))
      (node (ref "P2") (pin "11") (pinfunction "11_11") (pintype "unspecified"))
      (node (ref "P2") (pin "13") (pinfunction "13_13") (pintype "unspecified"))
      (node (ref "P2") (pin "15") (pinfunction "15_15") (pintype "unspecified"))
      (node (ref "P2") (pin "17") (pinfunction "17_17") (pintype "unspecified"))
      (node (ref "P2") (pin "3") (pinfunction "3_3") (pintype "unspecified"))
      (node (ref "P2") (pin "5") (pinfunction "5_5") (pintype "unspecified"))
      (node (ref "P2") (pin "7") (pinfunction "7_7") (pintype "unspecified"))
      (node (ref "P2") (pin "9") (pinfunction "9_9") (pintype "unspecified"))
      (node (ref "P22") (pin "1") (pinfunction "1_1") (pintype "unspecified"))
      (node (ref "P6") (pin "3") (pinfunction "3_3") (pintype "unspecified"))
      (node (ref "P9") (pin "3") (pinfunction "3_3") (pintype "unspecified"))
      (node (ref "R1") (pin "2") (pinfunction "2_2") (pintype "unspecified"))
      (node (ref "R10") (pin "2") (pinfunction "2_2") (pintype "unspecified"))
      (node (ref "R15") (pin "1") (pinfunction "1_1") (pintype "unspecified"))
      (node (ref "R17") (pin "1") (pinfunction "1_1") (pintype "unspecified"))
      (node (ref "R24") (pin "2") (pinfunction "2_2") (pintype "input"))
      (node (ref "R26") (pin "1") (pinfunction "1_1") (pintype "unspecified"))
      (node (ref "R33") (pin "1") (pinfunction "1_1") (pintype "unspecified"))
      (node (ref "R34") (pin "1") (pinfunction "1_1") (pintype "unspecified"))
      (node (ref "R40") (pin "1") (pinfunction "1_1") (pintype "unspecified"))
      (node (ref "R41") (pin "1") (pinfunction "1_1") (pintype "unspecified"))
      (node (ref "R49") (pin "1") (pinfunction "1_1") (pintype "unspecified"))
      (node (ref "R5") (pin "2") (pinfunction "2_2") (pintype "unspecified"))
      (node (ref "R52") (pin "1") (pinfunction "1_1") (pintype "unspecified"))
      (node (ref "R70") (pin "2") (pinfunction "2_2") (pintype "unspecified"))
      (node (ref "R75") (pin "2") (pinfunction "2_2") (pintype "unspecified"))
      (node (ref "R8") (pin "2") (pinfunction "2_2") (pintype "unspecified"))
      (node (ref "U11") (pin "16") (pinfunction "VCC_16") (pintype "unspecified"))
      (node (ref "U12") (pin "5") (pinfunction "VCC_5") (pintype "unspecified"))
      (node (ref "U13") (pin "5") (pinfunction "VCC_5") (pintype "unspecified"))
      (node (ref "U14") (pin "5") (pinfunction "VCC_5") (pintype "unspecified"))
      (node (ref "U15") (pin "16") (pinfunction "VCC_16") (pintype "unspecified"))
      (node (ref "U17") (pin "5") (pinfunction "5_5") (pintype "unspecified"))
      (node (ref "U2") (pin "3") (pinfunction "FB_3") (pintype "input"))
      (node (ref "U3") (pin "3") (pinfunction "IN_3") (pintype "unspecified"))
      (node (ref "U4") (pin "5") (pinfunction "VCC_5") (pintype "unspecified"))
      (node (ref "U6") (pin "16") (pinfunction "VCC_16") (pintype "unspecified"))
      (node (ref "U7") (pin "5") (pinfunction "VCC_5") (pintype "unspecified"))
      (node (ref "U8") (pin "16") (pinfunction "VCC_16") (pintype "unspecified"))
    )
    (net (code "6") (name "12V") (class "Default")
      (node (ref "C1") (pin "1") (pintype "unspecified"))
      (node (ref "C13") (pin "1") (pintype "unspecified"))
      (node (ref "D1") (pin "1") (pinfunction "1_1") (pintype "unspecified"))
      (node (ref "D27") (pin "1") (pinfunction "1_1") (pintype "unspecified"))
      (node (ref "H3") (pin "8") (pinfunction "8_8") (pintype "unspecified"))
      (node (ref "P15") (pin "1") (pinfunction "1_1") (pintype "unspecified"))
      (node (ref "P16") (pin "1") (pinfunction "1_1") (pintype "unspecified"))
      (node (ref "P2") (pin "22") (pinfunction "22_22") (pintype "unspecified"))
      (node (ref "P2") (pin "23") (pinfunction "23_23") (pintype "unspecified"))
      (node (ref "P2") (pin "24") (pinfunction "24_24") (pintype "unspecified"))
      (node (ref "P21") (pin "1") (pinfunction "1_1") (pintype "unspecified"))
      (node (ref "P3") (pin "2") (pintype "input"))
      (node (ref "P4") (pin "2") (pintype "input"))
      (node (ref "P5") (pin "1") (pinfunction "1_1") (pintype "unspecified"))
      (node (ref "P7") (pin "1") (pinfunction "1_1") (pintype "unspecified"))
      (node (ref "R4") (pin "2") (pinfunction "2_2") (pintype "unspecified"))
      (node (ref "U1") (pin "1") (pinfunction "IN_1") (pintype "unspecified"))
    )
    (net (code "7") (name "12V-SW") (class "Default")
      (node (ref "D7") (pin "2") (pinfunction "2_2") (pintype "input"))
      (node (ref "P7") (pin "2") (pinfunction "2_2") (pintype "unspecified"))
      (node (ref "U5") (pin "2") (pinfunction "2_2") (pintype "unspecified"))
    )
    (net (code "8") (name "12V_2") (class "Default")
      (node (ref "C50") (pin "2") (pinfunction "2_2") (pintype "unspecified"))
      (node (ref "C51") (pin "1") (pintype "unspecified"))
      (node (ref "D27") (pin "2") (pinfunction "2_2") (pintype "unspecified"))
      (node (ref "U19") (pin "1") (pinfunction "VIN_1") (pintype "input"))
    )
    (net (code "9") (name "12V_DIV") (class "Default")
      (node (ref "C18") (pin "1") (pintype "unspecified"))
      (node (ref "C22") (pin "1") (pintype "unspecified"))
      (node (ref "H5") (pin "8") (pinfunction "8_8") (pintype "unspecified"))
      (node (ref "H8") (pin "8") (pinfunction "8_8") (pintype "unspecified"))
      (node (ref "U1") (pin "3") (pinfunction "OUT_3") (pintype "unspecified"))
    )
    (net (code "10") (name "A_1A") (class "Default")
      (node (ref "H3") (pin "4") (pinfunction "4_4") (pintype "unspecified"))
      (node (ref "P8") (pin "3") (pinfunction "3_3") (pintype "unspecified"))
      (node (ref "R20") (pin "1") (pinfunction "1_1") (pintype "unspecified"))
    )
    (net (code "11") (name "A_1B") (class "Default")
      (node (ref "H3") (pin "3") (pinfunction "3_3") (pintype "unspecified"))
      (node (ref "P8") (pin "4") (pinfunction "4_4") (pintype "unspecified"))
      (node (ref "R22") (pin "1") (pinfunction "1_1") (pintype "unspecified"))
    )
    (net (code "12") (name "A_2A") (class "Default")
      (node (ref "H3") (pin "5") (pinfunction "5_5") (pintype "unspecified"))
      (node (ref "P8") (pin "2") (pinfunction "2_2") (pintype "unspecified"))
      (node (ref "R19") (pin "1") (pinfunction "1_1") (pintype "unspecified"))
    )
    (net (code "13") (name "A_2B") (class "Default")
      (node (ref "H3") (pin "6") (pinfunction "6_6") (pintype "unspecified"))
      (node (ref "P8") (pin "1") (pinfunction "1_1") (pintype "unspecified"))
      (node (ref "R18") (pin "1") (pinfunction "1_1") (pintype "unspecified"))
    )
    (net (code "14") (name "A_DIR_O") (class "Default")
      (node (ref "H2") (pin "1") (pinfunction "1_1") (pintype "unspecified"))
      (node (ref "U6") (pin "2") (pinfunction "Q2_2") (pintype "unspecified"))
    )
    (net (code "15") (name "A_STEP_O") (class "Default")
      (node (ref "H2") (pin "2") (pinfunction "2_2") (pintype "unspecified"))
      (node (ref "U6") (pin "1") (pinfunction "Q1_1") (pintype "unspecified"))
    )
    (net (code "16") (name "B_1A") (class "Default")
      (node (ref "H5") (pin "4") (pinfunction "4_4") (pintype "unspecified"))
      (node (ref "P10") (pin "3") (pinfunction "3_3") (pintype "unspecified"))
      (node (ref "R31") (pin "1") (pinfunction "1_1") (pintype "unspecified"))
    )
    (net (code "17") (name "B_1B") (class "Default")
      (node (ref "H5") (pin "3") (pinfunction "3_3") (pintype "unspecified"))
      (node (ref "P10") (pin "4") (pinfunction "4_4") (pintype "unspecified"))
      (node (ref "R32") (pin "1") (pinfunction "1_1") (pintype "unspecified"))
    )
    (net (code "18") (name "B_2A") (class "Default")
      (node (ref "H5") (pin "5") (pinfunction "5_5") (pintype "unspecified"))
      (node (ref "P10") (pin "2") (pinfunction "2_2") (pintype "unspecified"))
      (node (ref "R30") (pin "1") (pinfunction "1_1") (pintype "unspecified"))
    )
    (net (code "19") (name "B_2B") (class "Default")
      (node (ref "H5") (pin "6") (pinfunction "6_6") (pintype "unspecified"))
      (node (ref "P10") (pin "1") (pinfunction "1_1") (pintype "unspecified"))
      (node (ref "R27") (pin "1") (pinfunction "1_1") (pintype "unspecified"))
    )
    (net (code "20") (name "B_DIR_O") (class "Default")
      (node (ref "H4") (pin "1") (pinfunction "1_1") (pintype "unspecified"))
      (node (ref "U6") (pin "4") (pinfunction "Q4_4") (pintype "unspecified"))
    )
    (net (code "21") (name "B_STEP_O") (class "Default")
      (node (ref "H4") (pin "2") (pinfunction "2_2") (pintype "unspecified"))
      (node (ref "U6") (pin "3") (pinfunction "Q3_3") (pintype "unspecified"))
    )
    (net (code "22") (name "C_1A") (class "Default")
      (node (ref "H8") (pin "4") (pinfunction "4_4") (pintype "unspecified"))
      (node (ref "P14") (pin "3") (pinfunction "3_3") (pintype "unspecified"))
      (node (ref "R38") (pin "1") (pinfunction "1_1") (pintype "unspecified"))
    )
    (net (code "23") (name "C_1B") (class "Default")
      (node (ref "H8") (pin "3") (pinfunction "3_3") (pintype "unspecified"))
      (node (ref "P14") (pin "4") (pinfunction "4_4") (pintype "unspecified"))
      (node (ref "R39") (pin "1") (pinfunction "1_1") (pintype "unspecified"))
    )
    (net (code "24") (name "C_2A") (class "Default")
      (node (ref "H8") (pin "5") (pinfunction "5_5") (pintype "unspecified"))
      (node (ref "P14") (pin "2") (pinfunction "2_2") (pintype "unspecified"))
      (node (ref "R37") (pin "1") (pinfunction "1_1") (pintype "unspecified"))
    )
    (net (code "25") (name "C_2B") (class "Default")
      (node (ref "H8") (pin "6") (pinfunction "6_6") (pintype "unspecified"))
      (node (ref "P14") (pin "1") (pinfunction "1_1") (pintype "unspecified"))
      (node (ref "R36") (pin "1") (pinfunction "1_1") (pintype "unspecified"))
    )
    (net (code "26") (name "C_DIR_O") (class "Default")
      (node (ref "H7") (pin "1") (pinfunction "1_1") (pintype "unspecified"))
      (node (ref "U6") (pin "6") (pinfunction "Q6_6") (pintype "unspecified"))
    )
    (net (code "27") (name "C_STEP_O") (class "Default")
      (node (ref "H7") (pin "2") (pinfunction "2_2") (pintype "unspecified"))
      (node (ref "U6") (pin "5") (pinfunction "Q5_5") (pintype "unspecified"))
    )
    (net (code "28") (name "D1+") (class "Default")
      (node (ref "D22") (pin "3") (pinfunction "I/O2_3") (pintype "unspecified"))
      (node (ref "USB1") (pin "3") (pinfunction "D+_3") (pintype "unspecified"))
    )
    (net (code "29") (name "D1-") (class "Default")
      (node (ref "D22") (pin "1") (pinfunction "I/O1_1") (pintype "unspecified"))
      (node (ref "USB1") (pin "2") (pinfunction "D-_2") (pintype "unspecified"))
    )
    (net (code "36") (name "DM") (class "Default")
      (node (ref "D18") (pin "6") (pinfunction "I/O1_6") (pintype "unspecified"))
      (node (ref "U18") (pin "9") (pinfunction "DM_9") (pintype "unspecified"))
    )
    (net (code "37") (name "DM1") (class "Default")
      (node (ref "D22") (pin "6") (pinfunction "I/O1_6") (pintype "unspecified"))
      (node (ref "U18") (pin "7") (pinfunction "DM1_7") (pintype "unspecified"))
    )
    (net (code "38") (name "DM2") (class "Default")
      (node (ref "U18") (pin "5") (pinfunction "DM2_5") (pintype "unspecified"))
    )
    (net (code "39") (name "DM3") (class "Default")
      (node (ref "U18") (pin "3") (pinfunction "DM3_3") (pintype "unspecified"))
    )
    (net (code "40") (name "DM4") (class "Default")
      (node (ref "U17") (pin "3") (pinfunction "3_3") (pintype "unspecified"))
      (node (ref "U18") (pin "1") (pinfunction "DM4_1") (pintype "unspecified"))
    )
    (net (code "41") (name "DP") (class "Default")
      (node (ref "D18") (pin "4") (pinfunction "I/O2_4") (pintype "unspecified"))
      (node (ref "U18") (pin "10") (pinfunction "DP_10") (pintype "unspecified"))
    )
    (net (code "42") (name "DP1") (class "Default")
      (node (ref "D22") (pin "4") (pinfunction "I/O2_4") (pintype "unspecified"))
      (node (ref "U18") (pin "8") (pinfunction "DP1_8") (pintype "unspecified"))
    )
    (net (code "43") (name "DP2") (class "Default")
      (node (ref "U18") (pin "6") (pinfunction "DP2_6") (pintype "unspecified"))
    )
    (net (code "44") (name "DP3") (class "Default")
      (node (ref "U18") (pin "4") (pinfunction "DP3_4") (pintype "unspecified"))
    )
    (net (code "45") (name "DP4") (class "Default")
      (node (ref "U17") (pin "1") (pinfunction "1_1") (pintype "unspecified"))
      (node (ref "U18") (pin "2") (pinfunction "DP4_2") (pintype "unspecified"))
    )
    (net (code "46") (name "ESP_BOOT") (class "Default")
      (node (ref "K2") (pin "2") (pinfunction "2_2") (pintype "unspecified"))
      (node (ref "Q1") (pin "3") (pinfunction "C_3") (pintype "unspecified"))
      (node (ref "U9") (pin "25") (pinfunction "IO0_25") (pintype "unspecified"))
    )
    (net (code "47") (name "ESP_RST") (class "Default")
      (node (ref "C23") (pin "2") (pinfunction "2_2") (pintype "unspecified"))
      (node (ref "Q2") (pin "3") (pinfunction "C_3") (pintype "unspecified"))
      (node (ref "R28") (pin "1") (pinfunction "1_1") (pintype "input"))
      (node (ref "R35") (pin "2") (pinfunction "2_2") (pintype "unspecified"))
      (node (ref "U9") (pin "3") (pinfunction "EN_3") (pintype "unspecified"))
    )
    (net (code "48") (name "GND") (class "Default")
      (node (ref "C1") (pin "2") (pintype "unspecified"))
      (node (ref "C10") (pin "1") (pinfunction "1_1") (pintype "unspecified"))
      (node (ref "C11") (pin "2") (pinfunction "2_2") (pintype "unspecified"))
      (node (ref "C12") (pin "2") (pinfunction "2_2") (pintype "unspecified"))
      (node (ref "C13") (pin "2") (pintype "unspecified"))
      (node (ref "C14") (pin "1") (pinfunction "1_1") (pintype "unspecified"))
      (node (ref "C15") (pin "2") (pinfunction "2_2") (pintype "unspecified"))
      (node (ref "C16") (pin "1") (pinfunction "1_1") (pintype "unspecified"))
      (node (ref "C17") (pin "1") (pinfunction "1_1") (pintype "unspecified"))
      (node (ref "C18") (pin "2") (pintype "unspecified"))
      (node (ref "C19") (pin "1") (pinfunction "1_1") (pintype "unspecified"))
      (node (ref "C2") (pin "2") (pintype "unspecified"))
      (node (ref "C20") (pin "1") (pinfunction "1_1") (pintype "unspecified"))
      (node (ref "C21") (pin "2") (pinfunction "2_2") (pintype "unspecified"))
      (node (ref "C22") (pin "2") (pintype "unspecified"))
      (node (ref "C23") (pin "1") (pinfunction "1_1") (pintype "unspecified"))
      (node (ref "C24") (pin "1") (pinfunction "1_1") (pintype "unspecified"))
      (node (ref "C26") (pin "1") (pinfunction "1_1") (pintype "unspecified"))
      (node (ref "C28") (pin "2") (pinfunction "2_2") (pintype "unspecified"))
      (node (ref "C29") (pin "1") (pinfunction "1_1") (pintype "unspecified"))
      (node (ref "C3") (pin "2") (pinfunction "2_2") (pintype "unspecified"))
      (node (ref "C30") (pin "1") (pinfunction "1_1") (pintype "unspecified"))
      (node (ref "C31") (pin "1") (pinfunction "1_1") (pintype "unspecified"))
      (node (ref "C32") (pin "1") (pinfunction "1_1") (pintype "unspecified"))
      (node (ref "C33") (pin "2") (pinfunction "2_2") (pintype "unspecified"))
      (node (ref "C34") (pin "2") (pinfunction "2_2") (pintype "input"))
      (node (ref "C35") (pin "2") (pinfunction "2_2") (pintype "unspecified"))
      (node (ref "C36") (pin "2") (pinfunction "2_2") (pintype "unspecified"))
      (node (ref "C37") (pin "2") (pinfunction "2_2") (pintype "unspecified"))
      (node (ref "C38") (pin "1") (pinfunction "1_1") (pintype "unspecified"))
      (node (ref "C39") (pin "1") (pinfunction "1_1") (pintype "unspecified"))
      (node (ref "C4") (pin "1") (pinfunction "1_1") (pintype "unspecified"))
      (node (ref "C40") (pin "1") (pinfunction "1_1") (pintype "unspecified"))
      (node (ref "C42") (pin "1") (pinfunction "1_1") (pintype "unspecified"))
      (node (ref "C43") (pin "2") (pinfunction "2_2") (pintype "input"))
      (node (ref "C44") (pin "2") (pinfunction "2_2") (pintype "input"))
      (node (ref "C45") (pin "1") (pinfunction "1_1") (pintype "unspecified"))
      (node (ref "C49") (pin "2") (pinfunction "2_2") (pintype "input"))
      (node (ref "C5") (pin "2") (pinfunction "2_2") (pintype "unspecified"))
      (node (ref "C50") (pin "1") (pinfunction "1_1") (pintype "unspecified"))
      (node (ref "C51") (pin "2") (pintype "unspecified"))
      (node (ref "C52") (pin "2") (pinfunction "2_2") (pintype "input"))
      (node (ref "C6") (pin "2") (pinfunction "2_2") (pintype "input"))
      (node (ref "C7") (pin "2") (pinfunction "2_2") (pintype "input"))
      (node (ref "C8") (pin "1") (pinfunction "1_1") (pintype "input"))
      (node (ref "C9") (pin "1") (pinfunction "1_1") (pintype "input"))
      (node (ref "D10") (pin "1") (pinfunction "1_1") (pintype "input"))
      (node (ref "D13") (pin "1") (pinfunction "1_1") (pintype "input"))
      (node (ref "D14") (pin "2") (pinfunction "2_2") (pintype "unspecified"))
      (node (ref "D18") (pin "2") (pinfunction "GND_2") (pintype "unspecified"))
      (node (ref "D2") (pin "1") (pinfunction "1_1") (pintype "input"))
      (node (ref "D22") (pin "2") (pinfunction "GND_2") (pintype "unspecified"))
      (node (ref "D25") (pin "1") (pinfunction "1_1") (pintype "input"))
      (node (ref "D26") (pin "1") (pinfunction "1_1") (pintype "input"))
      (node (ref "D29") (pin "2") (pinfunction "2_2") (pintype "unspecified"))
      (node (ref "D3") (pin "2") (pinfunction "2_2") (pintype "unspecified"))
      (node (ref "D30") (pin "1") (pinfunction "1_1") (pintype "input"))
      (node (ref "D4") (pin "1") (pinfunction "1_1") (pintype "input"))
      (node (ref "D5") (pin "2") (pinfunction "2_2") (pintype "unspecified"))
      (node (ref "D6") (pin "1") (pinfunction "1_1") (pintype "input"))
      (node (ref "D7") (pin "1") (pinfunction "1_1") (pintype "input"))
      (node (ref "D8") (pin "1") (pinfunction "1_1") (pintype "input"))
      (node (ref "D9") (pin "1") (pinfunction "1_1") (pintype "input"))
      (node (ref "H1") (pin "2") (pinfunction "2_2") (pintype "unspecified"))
      (node (ref "H3") (pin "1") (pinfunction "1_1") (pintype "unspecified"))
      (node (ref "H3") (pin "7") (pinfunction "7_7") (pintype "unspecified"))
      (node (ref "H5") (pin "1") (pinfunction "1_1") (pintype "unspecified"))
      (node (ref "H5") (pin "7") (pinfunction "7_7") (pintype "unspecified"))
      (node (ref "H8") (pin "1") (pinfunction "1_1") (pintype "unspecified"))
      (node (ref "H8") (pin "7") (pinfunction "7_7") (pintype "unspecified"))
      (node (ref "H9") (pin "3") (pinfunction "3_3") (pintype "unspecified"))
      (node (ref "K1") (pin "1") (pinfunction "1_1") (pintype "unspecified"))
      (node (ref "K1") (pin "2") (pinfunction "2_2") (pintype "unspecified"))
      (node (ref "K2") (pin "1") (pinfunction "1_1") (pintype "unspecified"))
      (node (ref "P1") (pin "1") (pinfunction "1_1") (pintype "unspecified"))
      (node (ref "P1") (pin "11") (pinfunction "11_11") (pintype "unspecified"))
      (node (ref "P1") (pin "3") (pinfunction "3_3") (pintype "unspecified"))
      (node (ref "P1") (pin "5") (pinfunction "5_5") (pintype "unspecified"))
      (node (ref "P1") (pin "7") (pinfunction "7_7") (pintype "unspecified"))
      (node (ref "P1") (pin "9") (pinfunction "9_9") (pintype "unspecified"))
      (node (ref "P11") (pin "1") (pintype "input"))
      (node (ref "P12") (pin "2") (pintype "input"))
      (node (ref "P13") (pin "1") (pinfunction "1_1") (pintype "unspecified"))
      (node (ref "P15") (pin "4") (pinfunction "4_4") (pintype "unspecified"))
      (node (ref "P16") (pin "4") (pinfunction "4_4") (pintype "unspecified"))
      (node (ref "P17") (pin "2") (pintype "input"))
      (node (ref "P18") (pin "2") (pintype "input"))
      (node (ref "P19") (pin "2") (pinfunction "2_2") (pintype "input"))
      (node (ref "P2") (pin "19") (pinfunction "19_19") (pintype "unspecified"))
      (node (ref "P2") (pin "20") (pinfunction "20_20") (pintype "unspecified"))
      (node (ref "P2") (pin "21") (pinfunction "21_21") (pintype "unspecified"))
      (node (ref "P20") (pin "3") (pinfunction "3_3") (pintype "unspecified"))
      (node (ref "P21") (pin "3") (pinfunction "3_3") (pintype "unspecified"))
      (node (ref "P22") (pin "4") (pinfunction "4_4") (pintype "unspecified"))
      (node (ref "P24") (pin "4") (pinfunction "GND_4") (pintype "unspecified"))
      (node (ref "P24") (pin "5") (pinfunction "GND_5") (pintype "unspecified"))
      (node (ref "P24") (pin "6") (pinfunction "GND_6") (pintype "unspecified"))
      (node (ref "P3") (pin "1") (pintype "input"))
      (node (ref "P4") (pin "1") (pintype "input"))
      (node (ref "P5") (pin "2") (pinfunction "2_2") (pintype "unspecified"))
      (node (ref "P6") (pin "1") (pinfunction "1_1") (pintype "unspecified"))
      (node (ref "P7") (pin "3") (pinfunction "3_3") (pintype "unspecified"))
      (node (ref "P9") (pin "1") (pinfunction "1_1") (pintype "unspecified"))
      (node (ref "R13") (pin "2") (pinfunction "2_2") (pintype "input"))
      (node (ref "R16") (pin "2") (pinfunction "2_2") (pintype "unspecified"))
      (node (ref "R18") (pin "2") (pinfunction "2_2") (pintype "unspecified"))
      (node (ref "R19") (pin "2") (pinfunction "2_2") (pintype "unspecified"))
      (node (ref "R20") (pin "2") (pinfunction "2_2") (pintype "unspecified"))
      (node (ref "R22") (pin "2") (pinfunction "2_2") (pintype "unspecified"))
      (node (ref "R27") (pin "2") (pinfunction "2_2") (pintype "unspecified"))
      (node (ref "R30") (pin "2") (pinfunction "2_2") (pintype "unspecified"))
      (node (ref "R31") (pin "2") (pinfunction "2_2") (pintype "unspecified"))
      (node (ref "R32") (pin "2") (pinfunction "2_2") (pintype "unspecified"))
      (node (ref "R36") (pin "2") (pinfunction "2_2") (pintype "unspecified"))
      (node (ref "R37") (pin "2") (pinfunction "2_2") (pintype "unspecified"))
      (node (ref "R38") (pin "2") (pinfunction "2_2") (pintype "unspecified"))
      (node (ref "R39") (pin "2") (pinfunction "2_2") (pintype "unspecified"))
      (node (ref "R47") (pin "2") (pinfunction "2_2") (pintype "input"))
      (node (ref "R50") (pin "2") (pinfunction "2_2") (pintype "input"))
      (node (ref "R71") (pin "2") (pinfunction "2_2") (pintype "unspecified"))
      (node (ref "R9") (pin "2") (pinfunction "2_2") (pintype "unspecified"))
      (node (ref "U1") (pin "2") (pinfunction "TAB_2") (pintype "unspecified"))
      (node (ref "U10") (pin "3") (pinfunction "3_3") (pintype "unspecified"))
      (node (ref "U11") (pin "15") (pinfunction "GND_15") (pintype "unspecified"))
      (node (ref "U12") (pin "3") (pinfunction "GND_3") (pintype "unspecified"))
      (node (ref "U13") (pin "3") (pinfunction "GND_3") (pintype "unspecified"))
      (node (ref "U14") (pin "3") (pinfunction "GND_3") (pintype "unspecified"))
      (node (ref "U15") (pin "1") (pinfunction "GND_1") (pintype "unspecified"))
      (node (ref "U16") (pin "10") (pinfunction "GND_10") (pintype "unspecified"))
      (node (ref "U16") (pin "11") (pinfunction "GND_11") (pintype "unspecified"))
      (node (ref "U16") (pin "12") (pinfunction "GND_12") (pintype "unspecified"))
      (node (ref "U16") (pin "13") (pinfunction "GND_13") (pintype "unspecified"))
      (node (ref "U16") (pin "6") (pinfunction "VSS_6") (pintype "unspecified"))
      (node (ref "U17") (pin "2") (pinfunction "2_2") (pintype "unspecified"))
      (node (ref "U18") (pin "12") (pinfunction "GND_12") (pintype "unspecified"))
      (node (ref "U19") (pin "5") (pinfunction "GND_5") (pintype "input"))
      (node (ref "U19") (pin "6") (pinfunction "GND_6") (pintype "input"))
      (node (ref "U19") (pin "7") (pinfunction "GND_7") (pintype "input"))
      (node (ref "U19") (pin "8") (pinfunction "GND_8") (pintype "input"))
      (node (ref "U2") (pin "5") (pinfunction "GND_5") (pintype "input"))
      (node (ref "U2") (pin "6") (pinfunction "GND_6") (pintype "input"))
      (node (ref "U2") (pin "7") (pinfunction "GND_7") (pintype "input"))
      (node (ref "U2") (pin "8") (pinfunction "GND_8") (pintype "input"))
      (node (ref "U3") (pin "1") (pinfunction "GND_1") (pintype "unspecified"))
      (node (ref "U4") (pin "3") (pinfunction "GND_3") (pintype "unspecified"))
      (node (ref "U5") (pin "3") (pinfunction "3_3") (pintype "unspecified"))
      (node (ref "U6") (pin "13") (pinfunction "OE#_13") (pintype "unspecified"))
      (node (ref "U6") (pin "8") (pinfunction "GND_8") (pintype "unspecified"))
      (node (ref "U7") (pin "3") (pinfunction "GND_3") (pintype "unspecified"))
      (node (ref "U8") (pin "13") (pinfunction "OE#_13") (pintype "unspecified"))
      (node (ref "U8") (pin "8") (pinfunction "GND_8") (pintype "unspecified"))
      (node (ref "U9") (pin "1") (pinfunction "GND_1") (pintype "unspecified"))
      (node (ref "U9") (pin "15") (pinfunction "GND_15") (pintype "unspecified"))
      (node (ref "U9") (pin "38") (pinfunction "GND_38") (pintype "unspecified"))
      (node (ref "U9") (pin "39") (pinfunction "EP_39") (pintype "unspecified"))
      (node (ref "USB1") (pin "0") (pinfunction "0_0") (pintype "unspecified"))
      (node (ref "USB1") (pin "4") (pinfunction "GND_4") (pintype "unspecified"))
    )
    (net (code "49") (name "I2SO(0)") (class "Default")
      (node (ref "H1") (pin "1") (pinfunction "1_1") (pintype "unspecified"))
      (node (ref "U6") (pin "15") (pinfunction "Q0_15") (pintype "unspecified"))
    )
    (net (code "50") (name "I2SO(8)") (class "Default")
      (node (ref "H9") (pin "4") (pinfunction "4_4") (pintype "unspecified"))
      (node (ref "U8") (pin "15") (pinfunction "Q0_15") (pintype "unspecified"))
    )
    (net (code "51") (name "I2S_BCK") (class "Default")
      (node (ref "R16") (pin "1") (pinfunction "1_1") (pintype "unspecified"))
      (node (ref "U6") (pin "11") (pinfunction "SHCP_11") (pintype "unspecified"))
      (node (ref "U8") (pin "11") (pinfunction "SHCP_11") (pintype "unspecified"))
      (node (ref "U9") (pin "12") (pinfunction "IO27_12") (pintype "unspecified"))
    )
    (net (code "52") (name "I2S_DATA") (class "Default")
      (node (ref "U6") (pin "14") (pinfunction "DS_14") (pintype "unspecified"))
      (node (ref "U9") (pin "10") (pinfunction "IO25_10") (pintype "unspecified"))
    )
    (net (code "53") (name "I2S_MR#") (class "Default")
      (node (ref "C17") (pin "2") (pinfunction "2_2") (pintype "unspecified"))
      (node (ref "R24") (pin "1") (pinfunction "1_1") (pintype "input"))
      (node (ref "U6") (pin "10") (pinfunction "MR#_10") (pintype "unspecified"))
      (node (ref "U8") (pin "10") (pinfunction "MR#_10") (pintype "unspecified"))
    )
    (net (code "54") (name "I2S_WS") (class "Default")
      (node (ref "U6") (pin "12") (pinfunction "STCP_12") (pintype "unspecified"))
      (node (ref "U8") (pin "12") (pinfunction "STCP_12") (pintype "unspecified"))
      (node (ref "U9") (pin "11") (pinfunction "IO26_11") (pintype "unspecified"))
    )
    (net (code "55") (name "IO2") (class "Default")
      (node (ref "U7") (pin "2") (pinfunction "A_2") (pintype "unspecified"))
      (node (ref "U9") (pin "24") (pinfunction "IO2_24") (pintype "unspecified"))
    )
    (net (code "56") (name "IO2_OUT") (class "Default")
      (node (ref "P11") (pin "2") (pintype "input"))
      (node (ref "U7") (pin "4") (pinfunction "Y_4") (pintype "unspecified"))
    )
    (net (code "57") (name "IO4") (class "Default")
      (node (ref "R21") (pin "1") (pinfunction "1_1") (pintype "input"))
      (node (ref "U9") (pin "26") (pinfunction "IO4_26") (pintype "unspecified"))
    )
    (net (code "58") (name "IO4_OUT") (class "Default")
      (node (ref "D8") (pin "2") (pinfunction "2_2") (pintype "input"))
      (node (ref "P9") (pin "2") (pinfunction "2_2") (pintype "unspecified"))
      (node (ref "R17") (pin "2") (pinfunction "2_2") (pintype "unspecified"))
      (node (ref "R21") (pin "2") (pinfunction "2_2") (pintype "input"))
      (node (ref "R23") (pin "1") (pinfunction "1_1") (pintype "unspecified"))
    )
    (net (code "59") (name "IO12") (class "Default")
      (node (ref "R47") (pin "1") (pinfunction "1_1") (pintype "input"))
      (node (ref "U12") (pin "2") (pinfunction "A_2") (pintype "unspecified"))
      (node (ref "U9") (pin "14") (pinfunction "IO12_14") (pintype "unspecified"))
    )
    (net (code "60") (name "IO14") (class "Default")
      (node (ref "R42") (pin "1") (pinfunction "1_1") (pintype "input"))
      (node (ref "U9") (pin "13") (pinfunction "IO14_13") (pintype "unspecified"))
    )
    (net (code "61") (name "IO14_IN") (class "Default")
      (node (ref "P17") (pin "1") (pintype "input"))
      (node (ref "R40") (pin "2") (pinfunction "2_2") (pintype "unspecified"))
      (node (ref "R42") (pin "2") (pinfunction "2_2") (pintype "input"))
      (node (ref "R44") (pin "1") (pinfunction "1_1") (pintype "unspecified"))
    )
    (net (code "62") (name "IO15") (class "Default")
      (node (ref "R15") (pin "2") (pinfunction "2_2") (pintype "unspecified"))
      (node (ref "U5") (pin "4") (pinfunction "4_4") (pintype "unspecified"))
      (node (ref "U9") (pin "23") (pinfunction "IO15_23") (pintype "unspecified"))
    )
    (net (code "63") (name "IO22") (class "Default")
      (node (ref "R13") (pin "1") (pinfunction "1_1") (pintype "input"))
      (node (ref "U4") (pin "2") (pinfunction "A_2") (pintype "unspecified"))
      (node (ref "U9") (pin "36") (pinfunction "IO22_36") (pintype "unspecified"))
    )
    (net (code "64") (name "IO32") (class "Default")
      (node (ref "R29") (pin "1") (pinfunction "1_1") (pintype "input"))
      (node (ref "U9") (pin "8") (pinfunction "IO32_8") (pintype "unspecified"))
    )
    (net (code "65") (name "IO32_IN") (class "Default")
      (node (ref "C19") (pin "2") (pinfunction "2_2") (pintype "unspecified"))
      (node (ref "D9") (pin "2") (pinfunction "2_2") (pintype "input"))
      (node (ref "P12") (pin "1") (pintype "input"))
      (node (ref "R26") (pin "2") (pinfunction "2_2") (pintype "unspecified"))
      (node (ref "R29") (pin "2") (pinfunction "2_2") (pintype "input"))
    )
    (net (code "66") (name "IO33") (class "Default")
      (node (ref "R43") (pin "1") (pinfunction "1_1") (pintype "input"))
      (node (ref "U9") (pin "9") (pinfunction "IO33_9") (pintype "unspecified"))
    )
    (net (code "67") (name "IO33_IN") (class "Default")
      (node (ref "D13") (pin "2") (pinfunction "2_2") (pintype "input"))
      (node (ref "P18") (pin "1") (pintype "input"))
      (node (ref "R41") (pin "2") (pinfunction "2_2") (pintype "unspecified"))
      (node (ref "R43") (pin "2") (pinfunction "2_2") (pintype "input"))
      (node (ref "R45") (pin "1") (pinfunction "1_1") (pintype "unspecified"))
    )
    (net (code "68") (name "M_EN_O") (class "Default")
      (node (ref "P2") (pin "2") (pinfunction "2_2") (pintype "unspecified"))
      (node (ref "P2") (pin "4") (pinfunction "4_4") (pintype "unspecified"))
      (node (ref "P2") (pin "6") (pinfunction "6_6") (pintype "unspecified"))
      (node (ref "U8") (pin "1") (pinfunction "Q1_1") (pintype "unspecified"))
    )
    (net (code "69") (name "Net-(C3-Pad1)") (class "Default")
      (node (ref "C3") (pin "1") (pinfunction "1_1") (pintype "unspecified"))
      (node (ref "R3") (pin "2") (pinfunction "2_2") (pintype "unspecified"))
    )
    (net (code "70") (name "Net-(C5-Pad1)") (class "Default")
      (node (ref "C5") (pin "1") (pinfunction "1_1") (pintype "unspecified"))
      (node (ref "R7") (pin "2") (pinfunction "2_2") (pintype "unspecified"))
    )
    (net (code "71") (name "Net-(C11-Pad1)") (class "Default")
      (node (ref "C11") (pin "1") (pinfunction "1_1") (pintype "unspecified"))
      (node (ref "R12") (pin "2") (pinfunction "2_2") (pintype "unspecified"))
    )
    (net (code "72") (name "Net-(C14-Pad2)") (class "Default")
      (node (ref "C14") (pin "2") (pinfunction "2_2") (pintype "unspecified"))
      (node (ref "R23") (pin "2") (pinfunction "2_2") (pintype "unspecified"))
    )
    (net (code "73") (name "Net-(C20-Pad2)") (class "Default")
      (node (ref "C20") (pin "2") (pinfunction "2_2") (pintype "unspecified"))
      (node (ref "K1") (pin "3") (pinfunction "3_3") (pintype "unspecified"))
      (node (ref "K1") (pin "4") (pinfunction "4_4") (pintype "unspecified"))
      (node (ref "R25") (pin "2") (pinfunction "2_2") (pintype "unspecified"))
      (node (ref "R28") (pin "2") (pinfunction "2_2") (pintype "input"))
    )
    (net (code "74") (name "Net-(C30-Pad2)") (class "Default")
      (node (ref "C30") (pin "2") (pinfunction "2_2") (pintype "unspecified"))
      (node (ref "R44") (pin "2") (pinfunction "2_2") (pintype "unspecified"))
    )
    (net (code "75") (name "Net-(C31-Pad2)") (class "Default")
      (node (ref "C31") (pin "2") (pinfunction "2_2") (pintype "unspecified"))
      (node (ref "R45") (pin "2") (pinfunction "2_2") (pintype "unspecified"))
    )
    (net (code "76") (name "Net-(D3-Pad1)") (class "Default")
      (node (ref "D3") (pin "1") (pinfunction "1_1") (pintype "unspecified"))
      (node (ref "R4") (pin "1") (pinfunction "1_1") (pintype "unspecified"))
    )
    (net (code "77") (name "Net-(D5-Pad1)") (class "Default")
      (node (ref "D5") (pin "1") (pinfunction "1_1") (pintype "unspecified"))
      (node (ref "R8") (pin "1") (pinfunction "1_1") (pintype "unspecified"))
    )
    (net (code "78") (name "Net-(D16-A)") (class "Default")
      (node (ref "D16") (pin "2") (pinfunction "A_2") (pintype "input"))
      (node (ref "R52") (pin "2") (pinfunction "2_2") (pintype "unspecified"))
      (node (ref "U15") (pin "3") (pinfunction "RXD_3") (pintype "unspecified"))
    )
    (net (code "79") (name "Net-(D17-K)") (class "Default")
      (node (ref "D17") (pin "1") (pinfunction "K_1") (pintype "input"))
      (node (ref "U15") (pin "2") (pinfunction "TXD_2") (pintype "unspecified"))
    )
    (net (code "80") (name "Net-(D29-Pad1)") (class "Default")
      (node (ref "D29") (pin "1") (pinfunction "1_1") (pintype "unspecified"))
      (node (ref "R73") (pin "1") (pinfunction "1_1") (pintype "unspecified"))
    )
    (net (code "81") (name "Net-(H2-Pad3)") (class "Default")
      (node (ref "H2") (pin "3") (pinfunction "3_3") (pintype "unspecified"))
      (node (ref "H2") (pin "4") (pinfunction "4_4") (pintype "unspecified"))
    )
    (net (code "82") (name "Net-(H4-Pad3)") (class "Default")
      (node (ref "H4") (pin "3") (pinfunction "3_3") (pintype "unspecified"))
      (node (ref "H4") (pin "4") (pinfunction "4_4") (pintype "unspecified"))
    )
    (net (code "83") (name "Net-(H7-Pad3)") (class "Default")
      (node (ref "H7") (pin "3") (pinfunction "3_3") (pintype "unspecified"))
      (node (ref "H7") (pin "4") (pinfunction "4_4") (pintype "unspecified"))
    )
    (net (code "84") (name "Net-(Q1-B)") (class "Default")
      (node (ref "Q1") (pin "1") (pinfunction "B_1") (pintype "unspecified"))
      (node (ref "R53") (pin "2") (pinfunction "2_2") (pintype "unspecified"))
    )
    (net (code "85") (name "Net-(Q1-E)") (class "Default")
      (node (ref "Q1") (pin "2") (pinfunction "E_2") (pintype "unspecified"))
      (node (ref "R59") (pin "1") (pinfunction "1_1") (pintype "unspecified"))
      (node (ref "U15") (pin "13") (pinfunction "DTR#_13") (pintype "unspecified"))
    )
    (net (code "86") (name "Net-(Q2-B)") (class "Default")
      (node (ref "Q2") (pin "1") (pinfunction "B_1") (pintype "unspecified"))
      (node (ref "R59") (pin "2") (pinfunction "2_2") (pintype "unspecified"))
    )
    (net (code "87") (name "Net-(Q2-E)") (class "Default")
      (node (ref "Q2") (pin "2") (pinfunction "E_2") (pintype "unspecified"))
      (node (ref "R53") (pin "1") (pinfunction "1_1") (pintype "unspecified"))
      (node (ref "U15") (pin "14") (pinfunction "RTS#_14") (pintype "unspecified"))
    )
    (net (code "88") (name "Net-(R14-Pad2)") (class "Default")
      (node (ref "R14") (pin "2") (pinfunction "2_2") (pintype "unspecified"))
      (node (ref "U5") (pin "1") (pinfunction "1_1") (pintype "unspecified"))
    )
    (net (code "89") (name "Net-(R33-Pad2)") (class "Default")
      (node (ref "R33") (pin "2") (pinfunction "2_2") (pintype "unspecified"))
      (node (ref "U10") (pin "1") (pinfunction "1_1") (pintype "unspecified"))
    )
    (net (code "90") (name "Net-(U2-ON{slash}OFF)") (class "Default")
      (node (ref "R9") (pin "1") (pinfunction "1_1") (pintype "unspecified"))
      (node (ref "U2") (pin "4") (pinfunction "ON/OFF_4") (pintype "input"))
    )
    (net (code "91") (name "Net-(U2-OUTPUT)") (class "Default")
      (node (ref "D2") (pin "2") (pinfunction "2_2") (pintype "input"))
      (node (ref "L1") (pin "2") (pinfunction "2_2") (pintype "unspecified"))
      (node (ref "U2") (pin "2") (pinfunction "OUTPUT_2") (pintype "input"))
    )
    (net (code "92") (name "Net-(U6-Q7S)") (class "Default")
      (node (ref "U6") (pin "9") (pinfunction "Q7S_9") (pintype "unspecified"))
      (node (ref "U8") (pin "14") (pinfunction "DS_14") (pintype "unspecified"))
    )
    (net (code "93") (name "Net-(U11-C1+)") (class "Default")
      (node (ref "C25") (pin "2") (pinfunction "2_2") (pintype "unspecified"))
      (node (ref "U11") (pin "1") (pinfunction "C1+_1") (pintype "unspecified"))
    )
    (net (code "94") (name "Net-(U11-C1-)") (class "Default")
      (node (ref "C25") (pin "1") (pinfunction "1_1") (pintype "unspecified"))
      (node (ref "U11") (pin "3") (pinfunction "C1-_3") (pintype "unspecified"))
    )
    (net (code "95") (name "Net-(U11-C2+)") (class "Default")
      (node (ref "C27") (pin "2") (pinfunction "2_2") (pintype "unspecified"))
      (node (ref "U11") (pin "4") (pinfunction "C2+_4") (pintype "unspecified"))
    )
    (net (code "96") (name "Net-(U11-C2-)") (class "Default")
      (node (ref "C27") (pin "1") (pinfunction "1_1") (pintype "unspecified"))
      (node (ref "U11") (pin "5") (pinfunction "C2-_5") (pintype "unspecified"))
    )
    (net (code "97") (name "Net-(U11-V+)") (class "Default")
      (node (ref "C24") (pin "2") (pinfunction "2_2") (pintype "unspecified"))
      (node (ref "U11") (pin "2") (pinfunction "V+_2") (pintype "unspecified"))
    )
    (net (code "98") (name "Net-(U11-V-)") (class "Default")
      (node (ref "C28") (pin "1") (pinfunction "1_1") (pintype "unspecified"))
      (node (ref "U11") (pin "6") (pinfunction "V-_6") (pintype "unspecified"))
    )
    (net (code "99") (name "Net-(U15-UD+)") (class "Default")
      (node (ref "U15") (pin "5") (pinfunction "UD+_5") (pintype "unspecified"))
      (node (ref "U17") (pin "6") (pinfunction "6_6") (pintype "unspecified"))
    )
    (net (code "100") (name "Net-(U15-UD-)") (class "Default")
      (node (ref "U15") (pin "6") (pinfunction "UD-_6") (pintype "unspecified"))
      (node (ref "U17") (pin "4") (pinfunction "4_4") (pintype "unspecified"))
    )
    (net (code "101") (name "Net-(U15-V3)") (class "Default")
      (node (ref "C35") (pin "1") (pinfunction "1_1") (pintype "unspecified"))
      (node (ref "U15") (pin "4") (pinfunction "V3_4") (pintype "unspecified"))
    )
    (net (code "102") (name "Net-(U15-XI)") (class "Default")
      (node (ref "C36") (pin "1") (pinfunction "1_1") (pintype "unspecified"))
      (node (ref "U15") (pin "7") (pinfunction "XI_7") (pintype "unspecified"))
      (node (ref "Y1") (pin "2") (pinfunction "OSC2_2") (pintype "unspecified"))
    )
    (net (code "103") (name "Net-(U15-XO)") (class "Default")
      (node (ref "C37") (pin "1") (pinfunction "1_1") (pintype "unspecified"))
      (node (ref "U15") (pin "8") (pinfunction "XO_8") (pintype "unspecified"))
      (node (ref "Y1") (pin "1") (pinfunction "OSC1_1") (pintype "unspecified"))
    )
    (net (code "104") (name "Net-(U18-VDD18)") (class "Default")
      (node (ref "C43") (pin "1") (pinfunction "1_1") (pintype "input"))
      (node (ref "U18") (pin "14") (pinfunction "VDD18_14") (pintype "unspecified"))
    )
    (net (code "105") (name "Net-(U18-VDD33)") (class "Default")
      (node (ref "C44") (pin "1") (pinfunction "1_1") (pintype "input"))
      (node (ref "U18") (pin "13") (pinfunction "VDD33_13") (pintype "unspecified"))
    )
    (net (code "106") (name "Net-(U19-ON{slash}OFF)") (class "Default")
      (node (ref "R71") (pin "1") (pinfunction "1_1") (pintype "unspecified"))
      (node (ref "U19") (pin "4") (pinfunction "ON/OFF_4") (pintype "input"))
    )
    (net (code "107") (name "Net-(U19-OUTPUT)") (class "Default")
      (node (ref "D25") (pin "2") (pinfunction "2_2") (pintype "input"))
      (node (ref "L2") (pin "2") (pinfunction "2_2") (pintype "unspecified"))
      (node (ref "U19") (pin "2") (pinfunction "OUTPUT_2") (pintype "input"))
    )
    (net (code "108") (name "PROBE") (class "Default")
      (node (ref "R34") (pin "2") (pinfunction "2_2") (pintype "unspecified"))
      (node (ref "U10") (pin "4") (pinfunction "4_4") (pintype "unspecified"))
      (node (ref "U9") (pin "7") (pinfunction "IO35_7") (pintype "unspecified"))
    )
    (net (code "109") (name "PROBE_O") (class "Default")
      (node (ref "D10") (pin "2") (pinfunction "2_2") (pintype "input"))
      (node (ref "P13") (pin "2") (pinfunction "2_2") (pintype "unspecified"))
      (node (ref "U10") (pin "2") (pinfunction "2_2") (pintype "unspecified"))
    )
    (net (code "110") (name "PWM") (class "Default")
      (node (ref "R50") (pin "1") (pinfunction "1_1") (pintype "input"))
      (node (ref "U13") (pin "2") (pinfunction "A_2") (pintype "unspecified"))
      (node (ref "U14") (pin "2") (pinfunction "A_2") (pintype "unspecified"))
      (node (ref "U9") (pin "16") (pinfunction "IO13_16") (pintype "unspecified"))
    )
    (net (code "111") (name "PWM_5V") (class "Default")
      (node (ref "P20") (pin "1") (pinfunction "1_1") (pintype "unspecified"))
      (node (ref "U14") (pin "4") (pinfunction "Y_4") (pintype "unspecified"))
    )
    (net (code "112") (name "PWM_LAS") (class "Default")
      (node (ref "D30") (pin "2") (pinfunction "2_2") (pintype "input"))
      (node (ref "P21") (pin "2") (pinfunction "2_2") (pintype "unspecified"))
      (node (ref "U13") (pin "4") (pinfunction "Y_4") (pintype "unspecified"))
    )
    (net (code "115") (name "R1IN") (class "Default")
      (node (ref "P15") (pin "2") (pinfunction "2_2") (pintype "unspecified"))
      (node (ref "U11") (pin "13") (pinfunction "R1IN_13") (pintype "unspecified"))
    )
    (net (code "116") (name "R1OUT") (class "Default")
      (node (ref "D11") (pin "1") (pinfunction "K_1") (pintype "input"))
      (node (ref "U11") (pin "12") (pinfunction "R1OUT_12") (pintype "unspecified"))
    )
    (net (code "117") (name "R2IN") (class "Default")
      (node (ref "P16") (pin "2") (pinfunction "2_2") (pintype "unspecified"))
      (node (ref "U11") (pin "8") (pinfunction "R2IN_8") (pintype "unspecified"))
    )
    (net (code "118") (name "R2OUT") (class "Default")
      (node (ref "R48") (pin "1") (pinfunction "1_1") (pintype "unspecified"))
      (node (ref "U11") (pin "9") (pinfunction "R2OUT_9") (pintype "unspecified"))
    )
    (net (code "119") (name "RGB_OUT") (class "Default")
      (node (ref "D6") (pin "2") (pinfunction "2_2") (pintype "input"))
      (node (ref "P6") (pin "2") (pinfunction "2_2") (pintype "unspecified"))
      (node (ref "U4") (pin "4") (pinfunction "Y_4") (pintype "unspecified"))
    )
    (net (code "120") (name "RX2") (class "Default")
      (node (ref "P22") (pin "2") (pinfunction "2_2") (pintype "unspecified"))
      (node (ref "R58") (pin "2") (pinfunction "2_2") (pintype "unspecified"))
    )
    (net (code "121") (name "RXD") (class "Default")
      (node (ref "D11") (pin "2") (pinfunction "A_2") (pintype "input"))
      (node (ref "D14") (pin "1") (pinfunction "1_1") (pintype "unspecified"))
      (node (ref "D17") (pin "2") (pinfunction "A_2") (pintype "input"))
      (node (ref "H6") (pin "2") (pinfunction "2_2") (pintype "unspecified"))
      (node (ref "R51") (pin "1") (pinfunction "1_1") (pintype "unspecified"))
      (node (ref "U9") (pin "34") (pinfunction "RXD0_34") (pintype "unspecified"))
    )
    (net (code "122") (name "RXD2") (class "Default")
      (node (ref "H9") (pin "1") (pinfunction "1_1") (pintype "unspecified"))
      (node (ref "R48") (pin "2") (pinfunction "2_2") (pintype "unspecified"))
      (node (ref "R58") (pin "1") (pinfunction "1_1") (pintype "unspecified"))
      (node (ref "U9") (pin "27") (pinfunction "IO16_27") (pintype "unspecified"))
    )
    (net (code "123") (name "SD_CD") (class "Default")
      (node (ref "R60") (pin "1") (pinfunction "1_1") (pintype "unspecified"))
      (node (ref "U16") (pin "9") (pinfunction "CD_9") (pintype "unspecified"))
      (node (ref "U9") (pin "33") (pinfunction "IO21_33") (pintype "unspecified"))
    )
    (net (code "124") (name "SD_CS") (class "Default")
      (node (ref "R54") (pin "1") (pinfunction "1_1") (pintype "unspecified"))
      (node (ref "U16") (pin "2") (pinfunction "CD/DAT3_2") (pintype "unspecified"))
      (node (ref "U9") (pin "29") (pinfunction "IO5_29") (pintype "unspecified"))
    )
    (net (code "125") (name "SD_MISO") (class "Default")
      (node (ref "R57") (pin "1") (pinfunction "1_1") (pintype "unspecified"))
      (node (ref "U16") (pin "7") (pinfunction "DAT0_7") (pintype "unspecified"))
      (node (ref "U9") (pin "31") (pinfunction "IO19_31") (pintype "unspecified"))
    )
    (net (code "126") (name "SD_MOSI") (class "Default")
      (node (ref "R55") (pin "1") (pinfunction "1_1") (pintype "unspecified"))
      (node (ref "U16") (pin "3") (pinfunction "CMD_3") (pintype "unspecified"))
      (node (ref "U9") (pin "37") (pinfunction "IO23_37") (pintype "unspecified"))
    )
    (net (code "127") (name "SD_SCLK") (class "Default")
      (node (ref "U16") (pin "5") (pinfunction "CLX_5") (pintype "unspecified"))
      (node (ref "U9") (pin "30") (pinfunction "IO18_30") (pintype "unspecified"))
    )
    (net (code "128") (name "SW3_OUT") (class "Default")
      (node (ref "P19") (pin "1") (pinfunction "1_1") (pintype "input"))
      (node (ref "U12") (pin "4") (pinfunction "Y_4") (pintype "unspecified"))
    )
    (net (code "129") (name "T1IN") (class "Default")
      (node (ref "D12") (pin "2") (pinfunction "A_2") (pintype "input"))
      (node (ref "R49") (pin "2") (pinfunction "2_2") (pintype "unspecified"))
      (node (ref "U11") (pin "11") (pinfunction "T1IN_11") (pintype "unspecified"))
    )
    (net (code "130") (name "T1OUT") (class "Default")
      (node (ref "P15") (pin "3") (pinfunction "3_3") (pintype "unspecified"))
      (node (ref "U11") (pin "14") (pinfunction "T1OUT_14") (pintype "unspecified"))
    )
    (net (code "131") (name "T2IN") (class "Default")
      (node (ref "R46") (pin "1") (pinfunction "1_1") (pintype "unspecified"))
      (node (ref "U11") (pin "10") (pinfunction "T2IN_10") (pintype "unspecified"))
    )
    (net (code "132") (name "T2OUT") (class "Default")
      (node (ref "P16") (pin "3") (pinfunction "3_3") (pintype "unspecified"))
      (node (ref "U11") (pin "7") (pinfunction "T2OUT_7") (pintype "unspecified"))
    )
    (net (code "133") (name "TX2") (class "Default")
      (node (ref "P22") (pin "3") (pinfunction "3_3") (pintype "unspecified"))
      (node (ref "R56") (pin "2") (pinfunction "2_2") (pintype "unspecified"))
    )
    (net (code "134") (name "TXD") (class "Default")
      (node (ref "D12") (pin "1") (pinfunction "K_1") (pintype "input"))
      (node (ref "D16") (pin "1") (pinfunction "K_1") (pintype "input"))
      (node (ref "H6") (pin "1") (pinfunction "1_1") (pintype "unspecified"))
      (node (ref "U9") (pin "35") (pinfunction "TXD0_35") (pintype "unspecified"))
    )
    (net (code "135") (name "TXD2") (class "Default")
      (node (ref "H9") (pin "2") (pinfunction "2_2") (pintype "unspecified"))
      (node (ref "R46") (pin "2") (pinfunction "2_2") (pintype "unspecified"))
      (node (ref "R56") (pin "1") (pinfunction "1_1") (pintype "unspecified"))
      (node (ref "U9") (pin "28") (pinfunction "IO17_28") (pintype "unspecified"))
    )
    (net (code "136") (name "USB_DM") (class "Default")
      (node (ref "D18") (pin "1") (pinfunction "I/O1_1") (pintype "unspecified"))
      (node (ref "P24") (pin "2") (pinfunction "D-_2") (pintype "unspecified"))
    )
    (net (code "137") (name "USB_DP") (class "Default")
      (node (ref "D18") (pin "3") (pinfunction "I/O2_3") (pintype "unspecified"))
      (node (ref "P24") (pin "3") (pinfunction "D+_3") (pintype "unspecified"))
    )
    (net (code "139") (name "VIN_12V") (class "Default")
      (node (ref "C2") (pin "1") (pintype "unspecified"))
      (node (ref "C4") (pin "2") (pinfunction "2_2") (pintype "unspecified"))
      (node (ref "D1") (pin "2") (pinfunction "2_2") (pintype "unspecified"))
      (node (ref "R14") (pin "1") (pinfunction "1_1") (pintype "unspecified"))
      (node (ref "U2") (pin "1") (pinfunction "VIN_1") (pintype "input"))
    )
    (net (code "140") (name "VUSB") (class "Default")
      (node (ref "D18") (pin "5") (pinfunction "VBUS_5") (pintype "unspecified"))
      (node (ref "P24") (pin "1") (pinfunction "VBUS_1") (pintype "unspecified"))
      (node (ref "R70") (pin "1") (pinfunction "1_1") (pintype "unspecified"))
    )
    (net (code "141") (name "XIN") (class "Default")
      (node (ref "C39") (pin "2") (pinfunction "2_2") (pintype "unspecified"))
      (node (ref "U18") (pin "16") (pinfunction "XIN_16") (pintype "unspecified"))
      (node (ref "Y2") (pin "2") (pinfunction "OSC2_2") (pintype "unspecified"))
    )
    (net (code "142") (name "XOUT") (class "Default")
      (node (ref "C40") (pin "2") (pinfunction "2_2") (pintype "unspecified"))
      (node (ref "U18") (pin "15") (pinfunction "XOUT_15") (pintype "unspecified"))
      (node (ref "Y2") (pin "1") (pinfunction "OSC1_1") (pintype "unspecified"))
    )
    (net (code "143") (name "X_DIR_O") (class "Default")
      (node (ref "P2") (pin "10") (pinfunction "10_10") (pintype "unspecified"))
      (node (ref "U8") (pin "3") (pinfunction "Q3_3") (pintype "unspecified"))
    )
    (net (code "144") (name "X_LIMT") (class "Default")
      (node (ref "R2") (pin "2") (pinfunction "2_2") (pintype "unspecified"))
      (node (ref "U9") (pin "6") (pinfunction "IO34_6") (pintype "unspecified"))
    )
    (net (code "145") (name "X_LIMT_I") (class "Default")
      (node (ref "P1") (pin "2") (pinfunction "2_2") (pintype "unspecified"))
      (node (ref "P1") (pin "4") (pinfunction "4_4") (pintype "unspecified"))
      (node (ref "R1") (pin "1") (pinfunction "1_1") (pintype "unspecified"))
      (node (ref "R2") (pin "1") (pinfunction "1_1") (pintype "unspecified"))
      (node (ref "R3") (pin "1") (pinfunction "1_1") (pintype "unspecified"))
    )
    (net (code "146") (name "X_STEP_O") (class "Default")
      (node (ref "P2") (pin "8") (pinfunction "8_8") (pintype "unspecified"))
      (node (ref "U8") (pin "2") (pinfunction "Q2_2") (pintype "unspecified"))
    )
    (net (code "147") (name "Y_DIR_O") (class "Default")
      (node (ref "P2") (pin "14") (pinfunction "14_14") (pintype "unspecified"))
      (node (ref "U8") (pin "5") (pinfunction "Q5_5") (pintype "unspecified"))
    )
    (net (code "148") (name "Y_LIMT") (class "Default")
      (node (ref "R6") (pin "2") (pinfunction "2_2") (pintype "unspecified"))
      (node (ref "U9") (pin "5") (pinfunction "SENSOR_VN_5") (pintype "unspecified"))
    )
    (net (code "149") (name "Y_LIMT_I") (class "Default")
      (node (ref "P1") (pin "6") (pinfunction "6_6") (pintype "unspecified"))
      (node (ref "P1") (pin "8") (pinfunction "8_8") (pintype "unspecified"))
      (node (ref "R5") (pin "1") (pinfunction "1_1") (pintype "unspecified"))
      (node (ref "R6") (pin "1") (pinfunction "1_1") (pintype "unspecified"))
      (node (ref "R7") (pin "1") (pinfunction "1_1") (pintype "unspecified"))
    )
    (net (code "150") (name "Y_STEP_O") (class "Default")
      (node (ref "P2") (pin "12") (pinfunction "12_12") (pintype "unspecified"))
      (node (ref "U8") (pin "4") (pinfunction "Q4_4") (pintype "unspecified"))
    )
    (net (code "151") (name "Z_DIR_O") (class "Default")
      (node (ref "P2") (pin "18") (pinfunction "18_18") (pintype "unspecified"))
      (node (ref "U8") (pin "7") (pinfunction "Q7_7") (pintype "unspecified"))
    )
    (net (code "152") (name "Z_LIMT") (class "Default")
      (node (ref "R11") (pin "2") (pinfunction "2_2") (pintype "unspecified"))
      (node (ref "U9") (pin "4") (pinfunction "SENSOR_VP_4") (pintype "unspecified"))
    )
    (net (code "153") (name "Z_LIMT_I") (class "Default")
      (node (ref "P1") (pin "10") (pinfunction "10_10") (pintype "unspecified"))
      (node (ref "P1") (pin "12") (pinfunction "12_12") (pintype "unspecified"))
      (node (ref "R10") (pin "1") (pinfunction "1_1") (pintype "unspecified"))
      (node (ref "R11") (pin "1") (pinfunction "1_1") (pintype "unspecified"))
      (node (ref "R12") (pin "1") (pinfunction "1_1") (pintype "unspecified"))
    )
    (net (code "154") (name "Z_STEP_O") (class "Default")
      (node (ref "P2") (pin "16") (pinfunction "16_16") (pintype "unspecified"))
      (node (ref "U8") (pin "6") (pinfunction "Q6_6") (pintype "unspecified"))
    )
    (net (code "155") (name "unconnected-(P19-Pad3)") (class "Default")
      (node (ref "P19") (pin "3") (pinfunction "3_3") (pintype "input"))
    )
    (net (code "156") (name "unconnected-(P20-Pad2)") (class "Default")
      (node (ref "P20") (pin "2") (pinfunction "2_2") (pintype "unspecified+no_connect"))
    )
    (net (code "157") (name "unconnected-(U4-NC-Pad1)") (class "Default")
      (node (ref "U4") (pin "1") (pinfunction "NC_1") (pintype "unspecified"))
    )
    (net (code "158") (name "unconnected-(U7-NC-Pad1)") (class "Default")
      (node (ref "U7") (pin "1") (pinfunction "NC_1") (pintype "unspecified"))
    )
    (net (code "159") (name "unconnected-(U8-Q7S-Pad9)") (class "Default")
      (node (ref "U8") (pin "9") (pinfunction "Q7S_9") (pintype "unspecified"))
    )
    (net (code "160") (name "unconnected-(U9-CLK-Pad20)") (class "Default")
      (node (ref "U9") (pin "20") (pinfunction "CLK_20") (pintype "unspecified"))
    )
    (net (code "161") (name "unconnected-(U9-CMD-Pad19)") (class "Default")
      (node (ref "U9") (pin "19") (pinfunction "CMD_19") (pintype "unspecified"))
    )
    (net (code "162") (name "unconnected-(U9-NC-Pad32)") (class "Default")
      (node (ref "U9") (pin "32") (pinfunction "NC_32") (pintype "unspecified"))
    )
    (net (code "163") (name "unconnected-(U9-SD0-Pad21)") (class "Default")
      (node (ref "U9") (pin "21") (pinfunction "SD0_21") (pintype "unspecified"))
    )
    (net (code "164") (name "unconnected-(U9-SD1-Pad22)") (class "Default")
      (node (ref "U9") (pin "22") (pinfunction "SD1_22") (pintype "unspecified"))
    )
    (net (code "165") (name "unconnected-(U9-SD2-Pad17)") (class "Default")
      (node (ref "U9") (pin "17") (pinfunction "SD2_17") (pintype "unspecified"))
    )
    (net (code "166") (name "unconnected-(U9-SD3-Pad18)") (class "Default")
      (node (ref "U9") (pin "18") (pinfunction "SD3_18") (pintype "unspecified"))
    )
    (net (code "167") (name "unconnected-(U12-NC-Pad1)") (class "Default")
      (node (ref "U12") (pin "1") (pinfunction "NC_1") (pintype "unspecified"))
    )
    (net (code "168") (name "unconnected-(U13-NC-Pad1)") (class "Default")
      (node (ref "U13") (pin "1") (pinfunction "NC_1") (pintype "unspecified"))
    )
    (net (code "169") (name "unconnected-(U14-NC-Pad1)") (class "Default")
      (node (ref "U14") (pin "1") (pinfunction "NC_1") (pintype "unspecified"))
    )
    (net (code "170") (name "unconnected-(U15-CTS#-Pad9)") (class "Default")
      (node (ref "U15") (pin "9") (pinfunction "CTS#_9") (pintype "unspecified"))
    )
    (net (code "171") (name "unconnected-(U15-DCD#-Pad12)") (class "Default")
      (node (ref "U15") (pin "12") (pinfunction "DCD#_12") (pintype "unspecified"))
    )
    (net (code "172") (name "unconnected-(U15-DSR#-Pad10)") (class "Default")
      (node (ref "U15") (pin "10") (pinfunction "DSR#_10") (pintype "unspecified"))
    )
    (net (code "173") (name "unconnected-(U15-R232-Pad15)") (class "Default")
      (node (ref "U15") (pin "15") (pinfunction "R232_15") (pintype "unspecified"))
    )
    (net (code "174") (name "unconnected-(U15-RI#-Pad11)") (class "Default")
      (node (ref "U15") (pin "11") (pinfunction "RI#_11") (pintype "unspecified"))
    )
    (net (code "175") (name "unconnected-(U16-DAT1-Pad8)") (class "Default")
      (node (ref "U16") (pin "8") (pinfunction "DAT1_8") (pintype "unspecified"))
    )
    (net (code "176") (name "unconnected-(U16-DAT2-Pad1)") (class "Default")
      (node (ref "U16") (pin "1") (pinfunction "DAT2_1") (pintype "unspecified"))
    )
  )
)
